# uSlices_v3_1.net
KiCad netlist of a schematic drawn in EAGLE
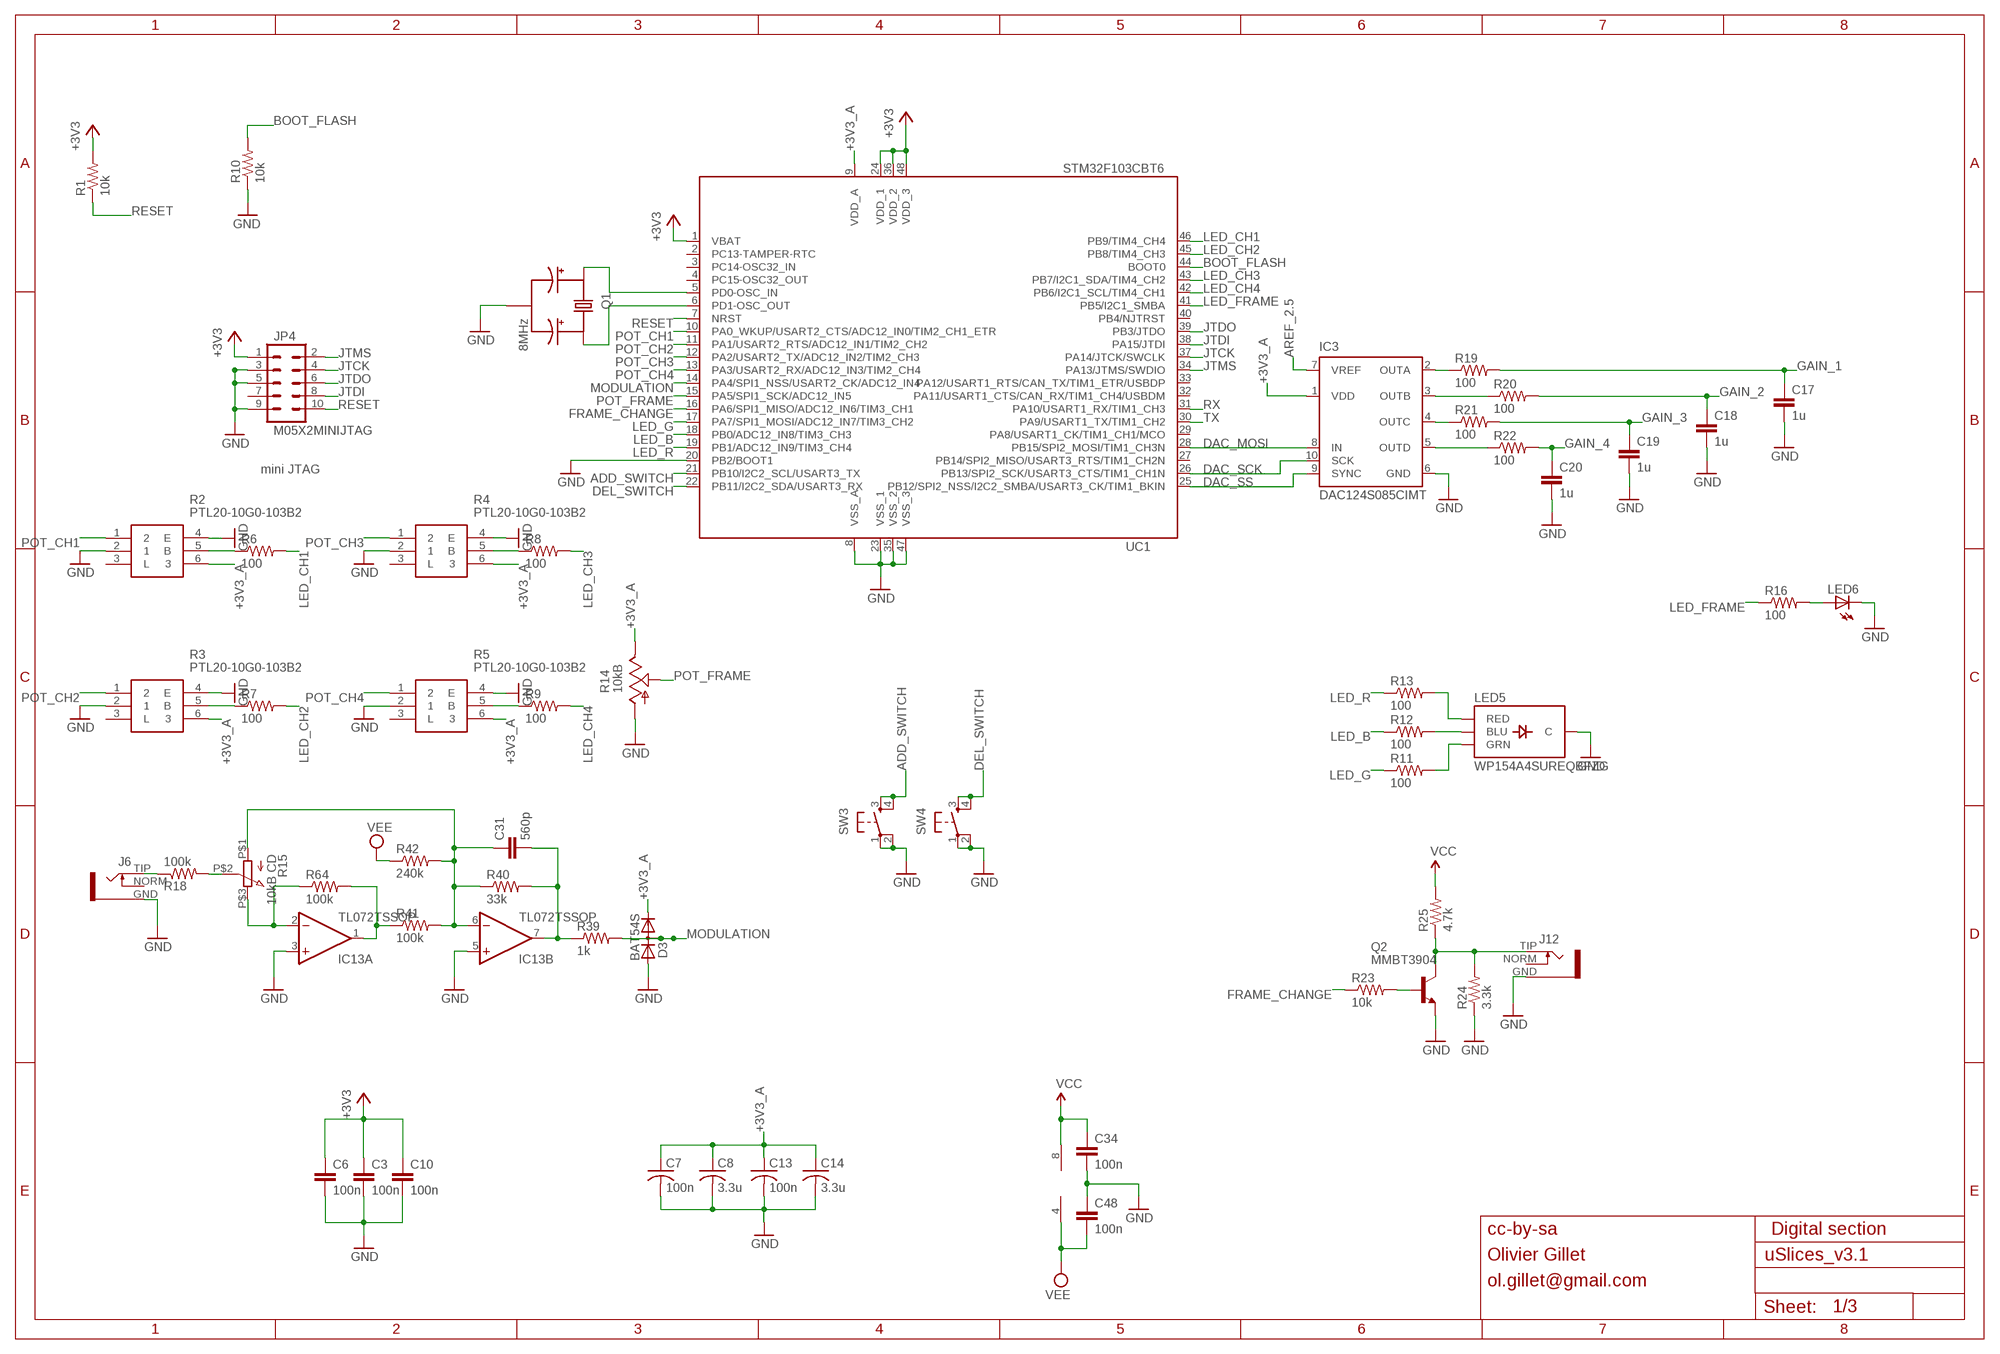
[diagram p0: schematic, sheet 1]
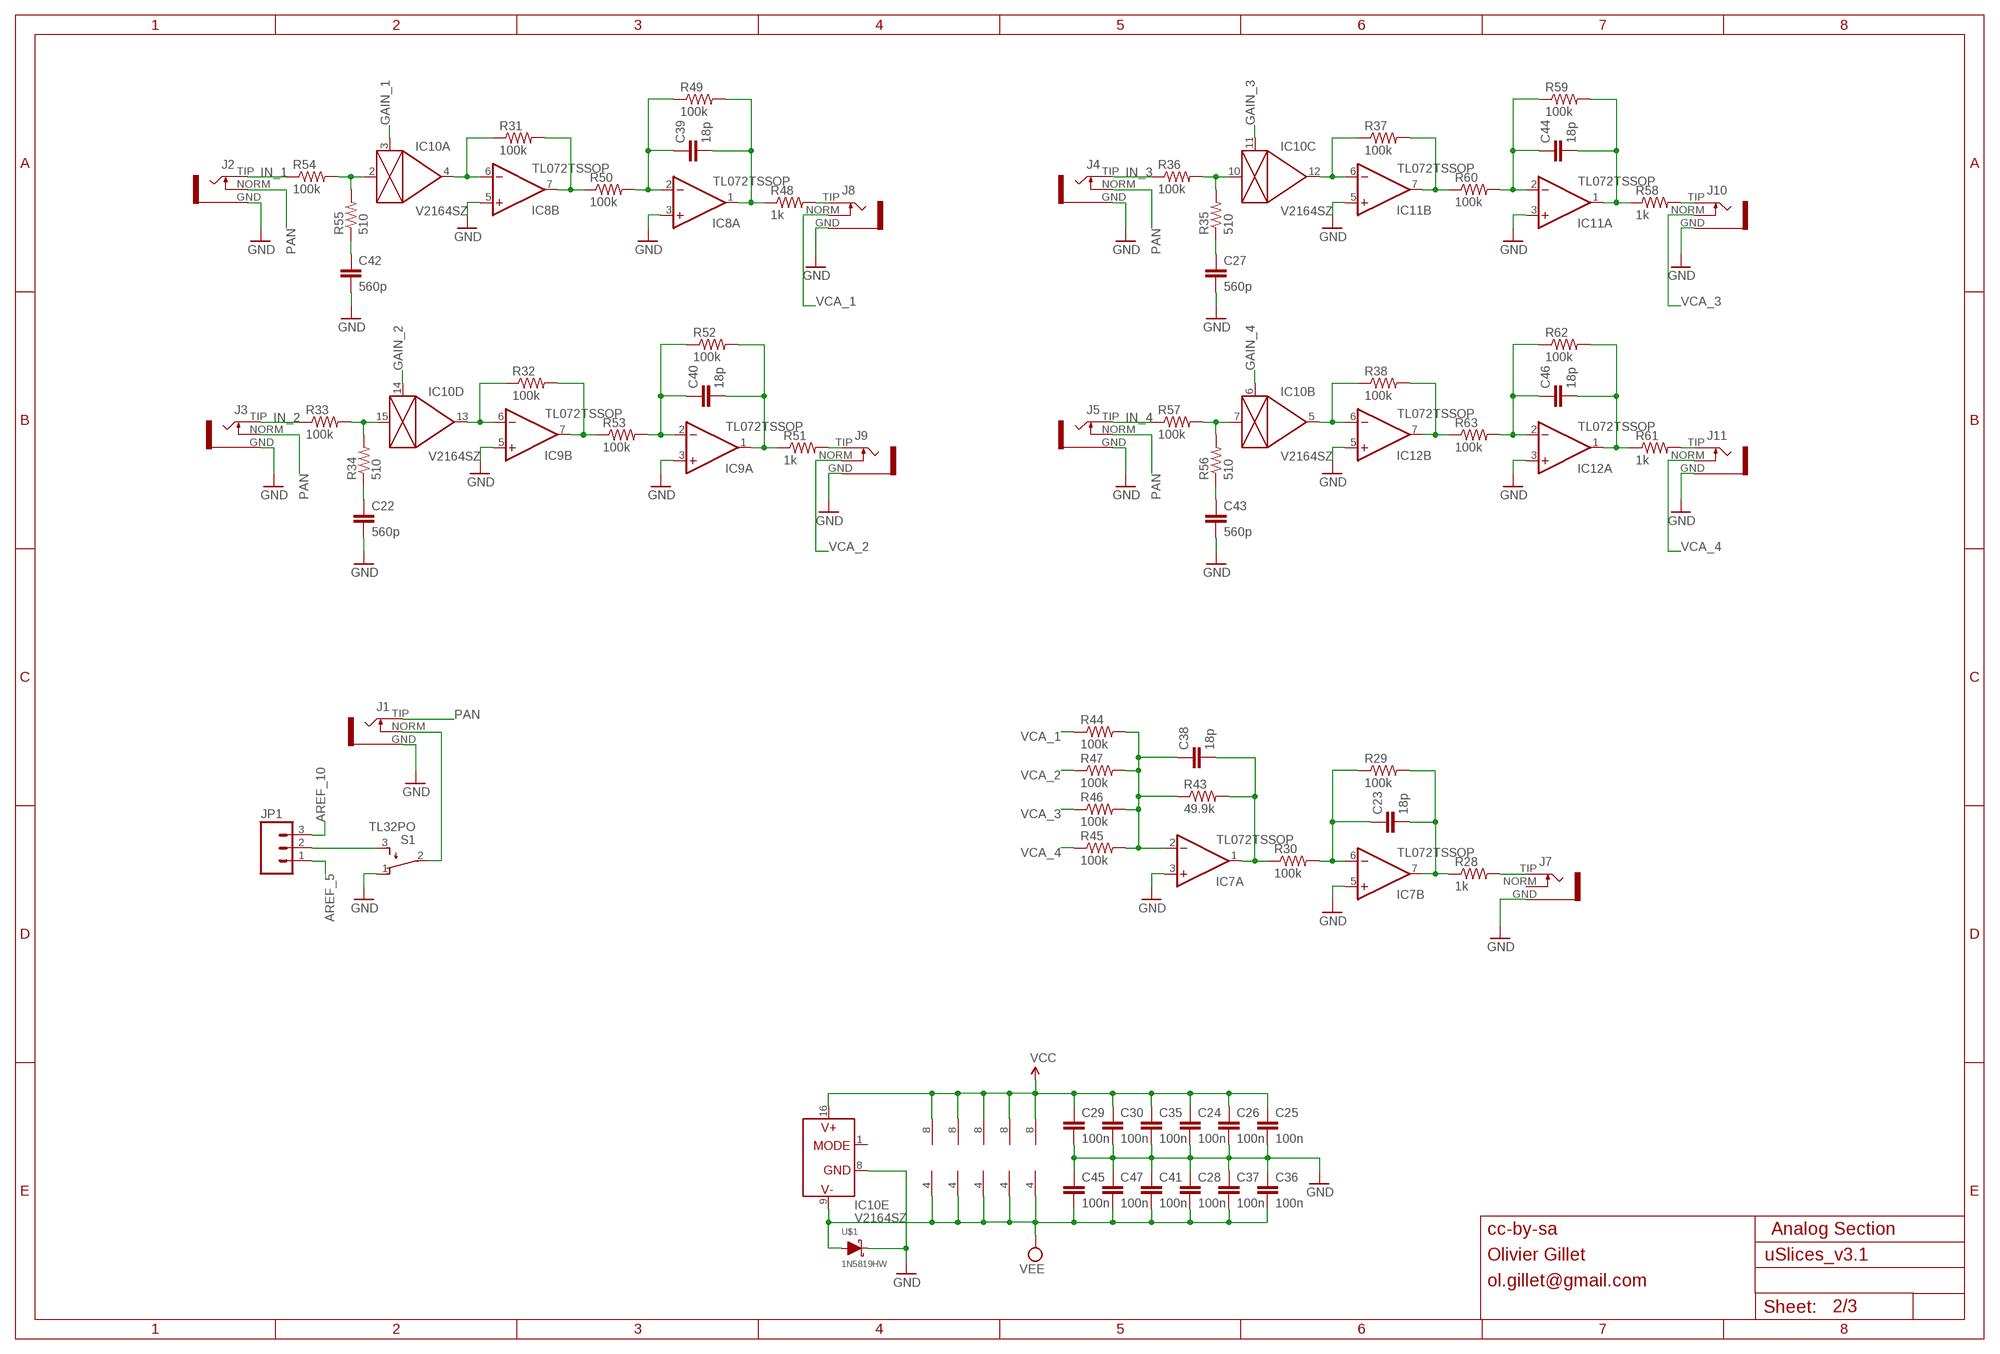
[diagram p1: schematic, sheet 2]
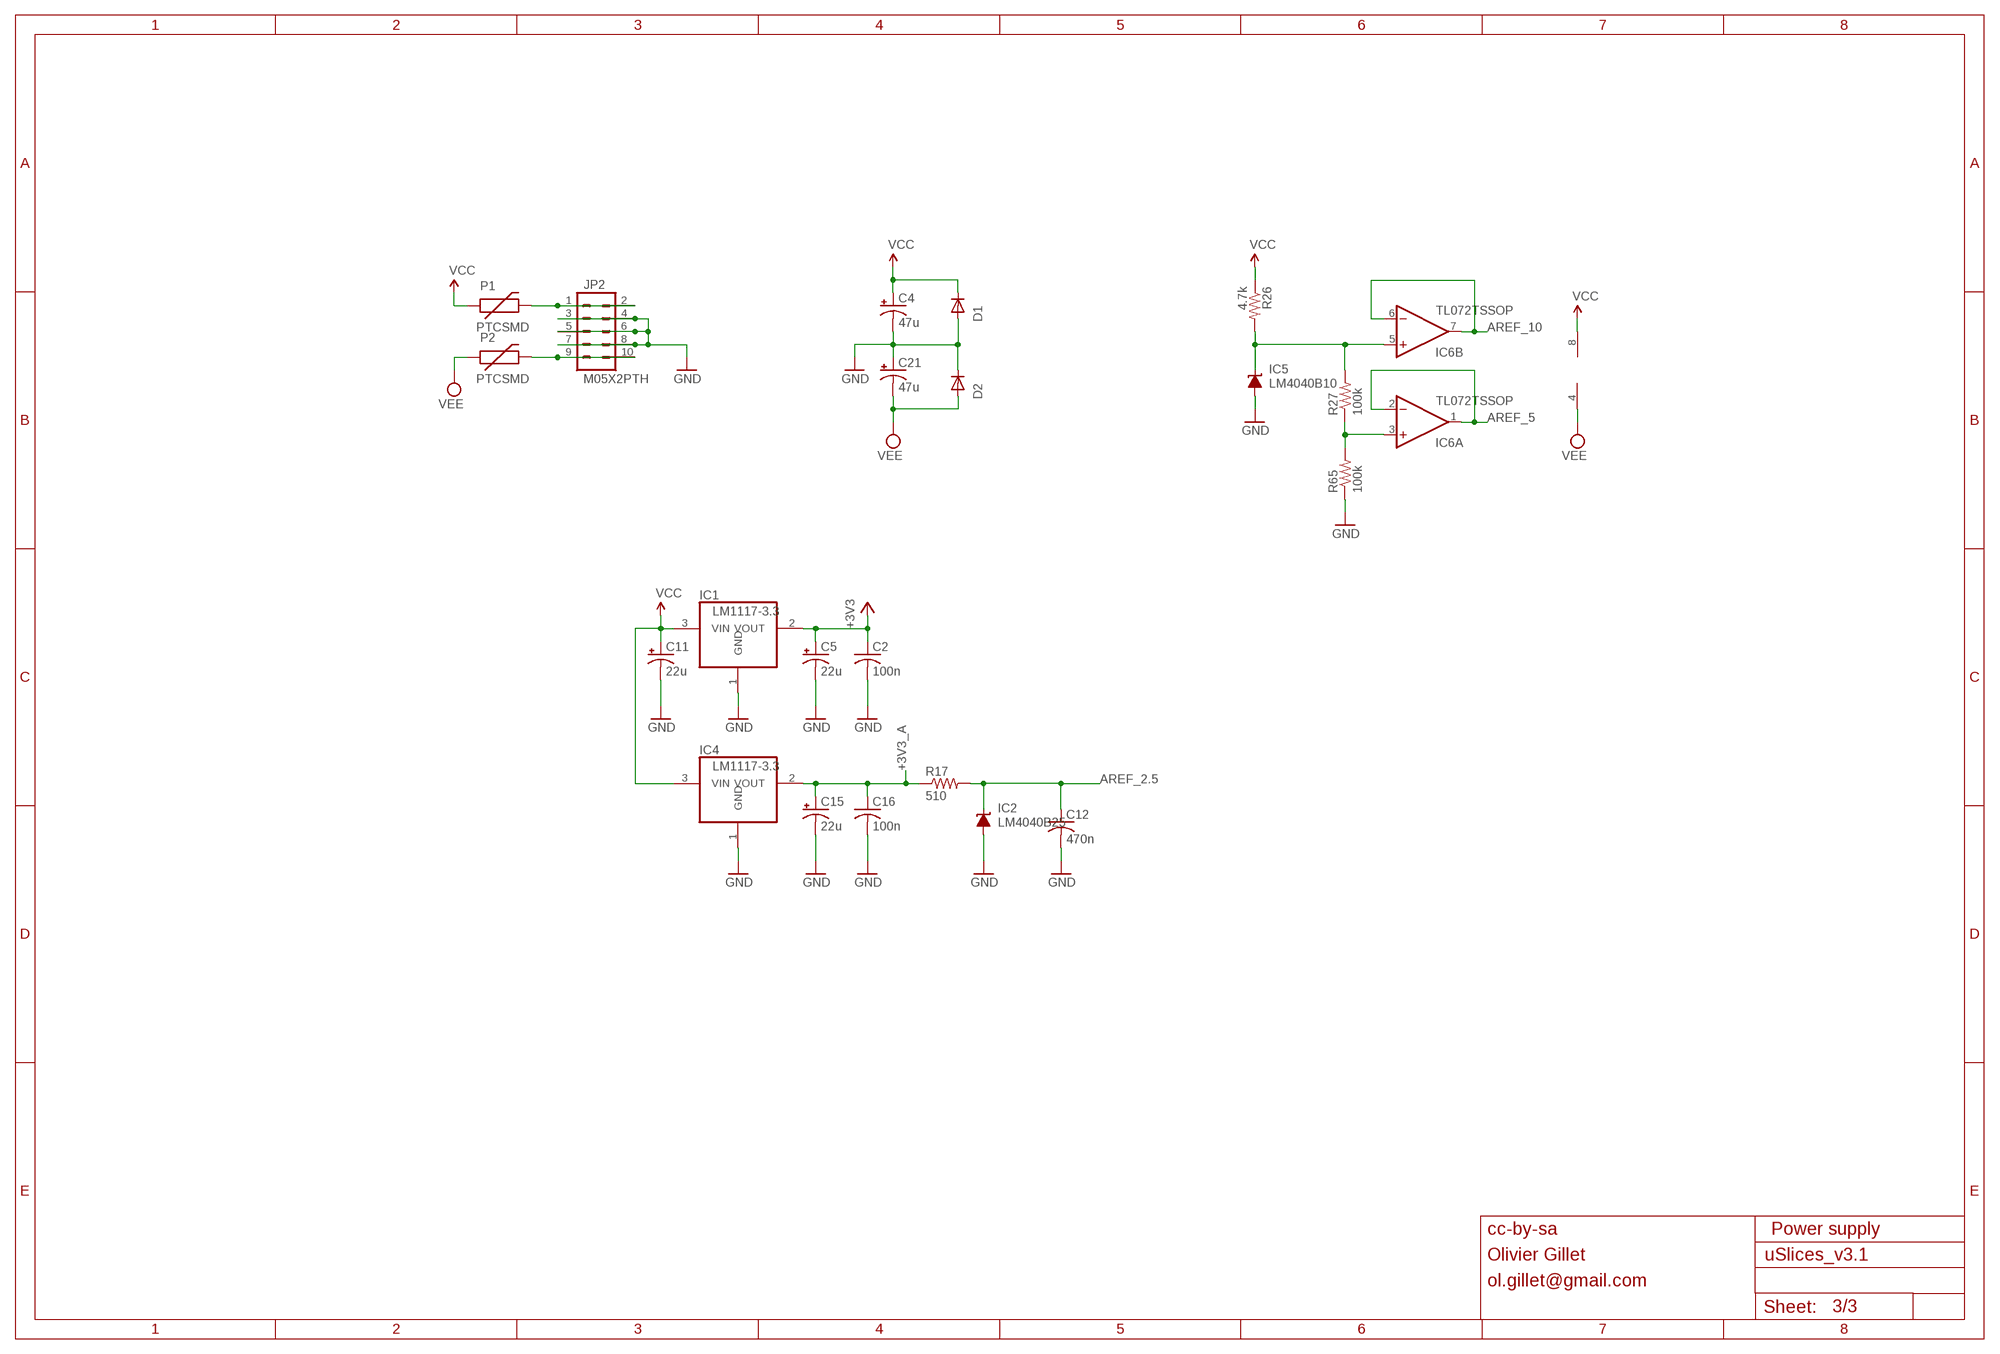
[diagram p2: schematic, sheet 3]

(export (version "E")
  (design (tool "Eeschema 10.0.6"))
  (components
    (comp (ref "C2")
      (value "100n")
      (footprint "eagle-import:C0603")
      (libsource (lib "eagle-import") (part "C-USC0603"))
    )
    (comp (ref "C4")
      (value "47u")
      (footprint "eagle-import:PANASONIC_D")
      (libsource (lib "eagle-import") (part "CPOL-USD"))
    )
    (comp (ref "C5")
      (value "22u")
      (footprint "eagle-import:PANASONIC_C")
      (libsource (lib "eagle-import") (part "CPOL-USC"))
    )
    (comp (ref "C11")
      (value "22u")
      (footprint "eagle-import:PANASONIC_C")
      (libsource (lib "eagle-import") (part "CPOL-USC"))
    )
    (comp (ref "C12")
      (value "470n")
      (footprint "eagle-import:C0603")
      (libsource (lib "eagle-import") (part "C-USC0603"))
    )
    (comp (ref "C15")
      (value "22u")
      (footprint "eagle-import:PANASONIC_C")
      (libsource (lib "eagle-import") (part "CPOL-USC"))
    )
    (comp (ref "C16")
      (value "100n")
      (footprint "eagle-import:C0603")
      (libsource (lib "eagle-import") (part "C-USC0603"))
    )
    (comp (ref "C21")
      (value "47u")
      (footprint "eagle-import:PANASONIC_D")
      (libsource (lib "eagle-import") (part "CPOL-USD"))
    )
    (comp (ref "D1")
      (value "1N5819HW")
      (footprint "eagle-import:SOD123")
      (libsource (lib "eagle-import") (part "DIODE-SOD123"))
    )
    (comp (ref "D2")
      (value "1N5819HW")
      (footprint "eagle-import:SOD123")
      (libsource (lib "eagle-import") (part "DIODE-SOD123"))
    )
    (comp (ref "IC1")
      (value "LM1117-3.3")
      (footprint "eagle-import:SOT223")
      (libsource (lib "eagle-import") (part "REG1117"))
    )
    (comp (ref "IC2")
      (value "LM4040B25")
      (footprint "eagle-import:DBZ_R-PDSO-G3")
      (libsource (lib "eagle-import") (part "LM4041DBZB12"))
    )
    (comp (ref "IC4")
      (value "LM1117-3.3")
      (footprint "eagle-import:SOT223")
      (libsource (lib "eagle-import") (part "REG1117"))
    )
    (comp (ref "IC5")
      (value "LM4040B10")
      (footprint "eagle-import:DBZ_R-PDSO-G3")
      (libsource (lib "eagle-import") (part "LM4041DBZB12"))
    )
    (comp (ref "IC6")
      (value "TL072TSSOP")
      (footprint "eagle-import:TSSOP-8")
      (libsource (lib "eagle-import") (part "TL072TSSOP"))
    )
    (comp (ref "JP2")
      (value "M05X2PTH")
      (footprint "eagle-import:AVR_ICSP")
      (libsource (lib "eagle-import") (part "M05X2PTH"))
    )
    (comp (ref "P1")
      (value "PTCSMD")
      (footprint "eagle-import:PTC-1206")
      (libsource (lib "eagle-import") (part "PTCSMD"))
    )
    (comp (ref "P2")
      (value "PTCSMD")
      (footprint "eagle-import:PTC-1206")
      (libsource (lib "eagle-import") (part "PTCSMD"))
    )
    (comp (ref "R17")
      (value "510")
      (footprint "eagle-import:R0603")
      (libsource (lib "eagle-import") (part "R-US_R0603"))
    )
    (comp (ref "R26")
      (value "4.7k")
      (footprint "eagle-import:R0603")
      (libsource (lib "eagle-import") (part "R-US_R0603"))
    )
    (comp (ref "R27")
      (value "100k")
      (footprint "eagle-import:R0603")
      (libsource (lib "eagle-import") (part "R-US_R0603"))
    )
    (comp (ref "R65")
      (value "100k")
      (footprint "eagle-import:R0603")
      (libsource (lib "eagle-import") (part "R-US_R0603"))
    )
    (comp (ref "C22")
      (value "560p")
      (footprint "eagle-import:PARTS_AMAN_RESISTOR_0603")
      (libsource (lib "eagle-import") (part "PARTS_AMAN_CAPACITOR"))
    )
    (comp (ref "C23")
      (value "18p")
      (footprint "eagle-import:PARTS_AMAN_RESISTOR_0603")
      (libsource (lib "eagle-import") (part "PARTS_AMAN_CAPACITOR"))
    )
    (comp (ref "C24")
      (value "100n")
      (footprint "eagle-import:PARTS_AMAN_RESISTOR_0603")
      (libsource (lib "eagle-import") (part "PARTS_AMAN_CAPACITOR"))
    )
    (comp (ref "C25")
      (value "100n")
      (footprint "eagle-import:PARTS_AMAN_RESISTOR_0603")
      (libsource (lib "eagle-import") (part "PARTS_AMAN_CAPACITOR"))
    )
    (comp (ref "C26")
      (value "100n")
      (footprint "eagle-import:PARTS_AMAN_RESISTOR_0603")
      (libsource (lib "eagle-import") (part "PARTS_AMAN_CAPACITOR"))
    )
    (comp (ref "C27")
      (value "560p")
      (footprint "eagle-import:PARTS_AMAN_RESISTOR_0603")
      (libsource (lib "eagle-import") (part "PARTS_AMAN_CAPACITOR"))
    )
    (comp (ref "C28")
      (value "100n")
      (footprint "eagle-import:PARTS_AMAN_RESISTOR_0603")
      (libsource (lib "eagle-import") (part "PARTS_AMAN_CAPACITOR"))
    )
    (comp (ref "C29")
      (value "100n")
      (footprint "eagle-import:PARTS_AMAN_RESISTOR_0603")
      (libsource (lib "eagle-import") (part "PARTS_AMAN_CAPACITOR"))
    )
    (comp (ref "C30")
      (value "100n")
      (footprint "eagle-import:PARTS_AMAN_RESISTOR_0603")
      (libsource (lib "eagle-import") (part "PARTS_AMAN_CAPACITOR"))
    )
    (comp (ref "C35")
      (value "100n")
      (footprint "eagle-import:PARTS_AMAN_RESISTOR_0603")
      (libsource (lib "eagle-import") (part "PARTS_AMAN_CAPACITOR"))
    )
    (comp (ref "C36")
      (value "100n")
      (footprint "eagle-import:PARTS_AMAN_RESISTOR_0603")
      (libsource (lib "eagle-import") (part "PARTS_AMAN_CAPACITOR"))
    )
    (comp (ref "C37")
      (value "100n")
      (footprint "eagle-import:PARTS_AMAN_RESISTOR_0603")
      (libsource (lib "eagle-import") (part "PARTS_AMAN_CAPACITOR"))
    )
    (comp (ref "C38")
      (value "18p")
      (footprint "eagle-import:PARTS_AMAN_RESISTOR_0603")
      (libsource (lib "eagle-import") (part "PARTS_AMAN_CAPACITOR"))
    )
    (comp (ref "C39")
      (value "18p")
      (footprint "eagle-import:PARTS_AMAN_RESISTOR_0603")
      (libsource (lib "eagle-import") (part "PARTS_AMAN_CAPACITOR"))
    )
    (comp (ref "C40")
      (value "18p")
      (footprint "eagle-import:PARTS_AMAN_RESISTOR_0603")
      (libsource (lib "eagle-import") (part "PARTS_AMAN_CAPACITOR"))
    )
    (comp (ref "C41")
      (value "100n")
      (footprint "eagle-import:PARTS_AMAN_RESISTOR_0603")
      (libsource (lib "eagle-import") (part "PARTS_AMAN_CAPACITOR"))
    )
    (comp (ref "C42")
      (value "560p")
      (footprint "eagle-import:PARTS_AMAN_RESISTOR_0603")
      (libsource (lib "eagle-import") (part "PARTS_AMAN_CAPACITOR"))
    )
    (comp (ref "C43")
      (value "560p")
      (footprint "eagle-import:PARTS_AMAN_RESISTOR_0603")
      (libsource (lib "eagle-import") (part "PARTS_AMAN_CAPACITOR"))
    )
    (comp (ref "C44")
      (value "18p")
      (footprint "eagle-import:PARTS_AMAN_RESISTOR_0603")
      (libsource (lib "eagle-import") (part "PARTS_AMAN_CAPACITOR"))
    )
    (comp (ref "C45")
      (value "100n")
      (footprint "eagle-import:PARTS_AMAN_RESISTOR_0603")
      (libsource (lib "eagle-import") (part "PARTS_AMAN_CAPACITOR"))
    )
    (comp (ref "C46")
      (value "18p")
      (footprint "eagle-import:PARTS_AMAN_RESISTOR_0603")
      (libsource (lib "eagle-import") (part "PARTS_AMAN_CAPACITOR"))
    )
    (comp (ref "C47")
      (value "100n")
      (footprint "eagle-import:PARTS_AMAN_RESISTOR_0603")
      (libsource (lib "eagle-import") (part "PARTS_AMAN_CAPACITOR"))
    )
    (comp (ref "IC7")
      (value "TL072TSSOP")
      (footprint "eagle-import:TSSOP-8")
      (libsource (lib "eagle-import") (part "TL072TSSOP"))
    )
    (comp (ref "IC8")
      (value "TL072TSSOP")
      (footprint "eagle-import:TSSOP-8")
      (libsource (lib "eagle-import") (part "TL072TSSOP"))
    )
    (comp (ref "IC9")
      (value "TL072TSSOP")
      (footprint "eagle-import:TSSOP-8")
      (libsource (lib "eagle-import") (part "TL072TSSOP"))
    )
    (comp (ref "IC10")
      (value "V2164SZ")
      (footprint "eagle-import:SOIC16N")
      (libsource (lib "eagle-import") (part "SSM2164S"))
    )
    (comp (ref "IC11")
      (value "TL072TSSOP")
      (footprint "eagle-import:TSSOP-8")
      (libsource (lib "eagle-import") (part "TL072TSSOP"))
    )
    (comp (ref "IC12")
      (value "TL072TSSOP")
      (footprint "eagle-import:TSSOP-8")
      (libsource (lib "eagle-import") (part "TL072TSSOP"))
    )
    (comp (ref "J1")
      (value "INSTRUO_S_JACK_S2_INV")
      (footprint "eagle-import:INSTRUO_S_JACK_S2_INV")
      (libsource (lib "eagle-import") (part "INSTRUO_S_JACK_S2_INV"))
    )
    (comp (ref "J2")
      (value "INSTRUO_S_JACK_S2_INV")
      (footprint "eagle-import:INSTRUO_S_JACK_S2_INV")
      (libsource (lib "eagle-import") (part "INSTRUO_S_JACK_S2_INV"))
    )
    (comp (ref "J3")
      (value "INSTRUO_S_JACK_S2_INV")
      (footprint "eagle-import:INSTRUO_S_JACK_S2_INV")
      (libsource (lib "eagle-import") (part "INSTRUO_S_JACK_S2_INV"))
    )
    (comp (ref "J4")
      (value "INSTRUO_S_JACK_S2_INV")
      (footprint "eagle-import:INSTRUO_S_JACK_S2_INV")
      (libsource (lib "eagle-import") (part "INSTRUO_S_JACK_S2_INV"))
    )
    (comp (ref "J5")
      (value "INSTRUO_S_JACK_S2_INV")
      (footprint "eagle-import:INSTRUO_S_JACK_S2_INV")
      (libsource (lib "eagle-import") (part "INSTRUO_S_JACK_S2_INV"))
    )
    (comp (ref "J7")
      (value "INSTRUO_S_JACK_S2_INV")
      (footprint "eagle-import:INSTRUO_S_JACK_S2_INV")
      (libsource (lib "eagle-import") (part "INSTRUO_S_JACK_S2_INV"))
    )
    (comp (ref "J8")
      (value "INSTRUO_S_JACK_S2_INV")
      (footprint "eagle-import:INSTRUO_S_JACK_S2_INV")
      (libsource (lib "eagle-import") (part "INSTRUO_S_JACK_S2_INV"))
    )
    (comp (ref "J9")
      (value "INSTRUO_S_JACK_S2_INV")
      (footprint "eagle-import:INSTRUO_S_JACK_S2_INV")
      (libsource (lib "eagle-import") (part "INSTRUO_S_JACK_S2_INV"))
    )
    (comp (ref "J10")
      (value "INSTRUO_S_JACK_S2_INV")
      (footprint "eagle-import:INSTRUO_S_JACK_S2_INV")
      (libsource (lib "eagle-import") (part "INSTRUO_S_JACK_S2_INV"))
    )
    (comp (ref "J11")
      (value "INSTRUO_S_JACK_S2_INV")
      (footprint "eagle-import:INSTRUO_S_JACK_S2_INV")
      (libsource (lib "eagle-import") (part "INSTRUO_S_JACK_S2_INV"))
    )
    (comp (ref "JP1")
      (value "M03PTH")
      (footprint "eagle-import:1X03")
      (libsource (lib "eagle-import") (part "M03PTH"))
    )
    (comp (ref "R28")
      (value "1k")
      (footprint "eagle-import:PARTS_AMAN_RESISTOR_0603")
      (libsource (lib "eagle-import") (part "PARTS_AMAN_RESISTOR"))
    )
    (comp (ref "R29")
      (value "100k")
      (footprint "eagle-import:PARTS_AMAN_RESISTOR_0603")
      (libsource (lib "eagle-import") (part "PARTS_AMAN_RESISTOR"))
    )
    (comp (ref "R30")
      (value "100k")
      (footprint "eagle-import:PARTS_AMAN_RESISTOR_0603")
      (libsource (lib "eagle-import") (part "PARTS_AMAN_RESISTOR"))
    )
    (comp (ref "R31")
      (value "100k")
      (footprint "eagle-import:PARTS_AMAN_RESISTOR_0603")
      (libsource (lib "eagle-import") (part "PARTS_AMAN_RESISTOR"))
    )
    (comp (ref "R32")
      (value "100k")
      (footprint "eagle-import:PARTS_AMAN_RESISTOR_0603")
      (libsource (lib "eagle-import") (part "PARTS_AMAN_RESISTOR"))
    )
    (comp (ref "R33")
      (value "100k")
      (footprint "eagle-import:PARTS_AMAN_RESISTOR_0603")
      (libsource (lib "eagle-import") (part "PARTS_AMAN_RESISTOR"))
    )
    (comp (ref "R34")
      (value "510")
      (footprint "eagle-import:PARTS_AMAN_RESISTOR_0603")
      (libsource (lib "eagle-import") (part "PARTS_AMAN_RESISTOR"))
    )
    (comp (ref "R35")
      (value "510")
      (footprint "eagle-import:PARTS_AMAN_RESISTOR_0603")
      (libsource (lib "eagle-import") (part "PARTS_AMAN_RESISTOR"))
    )
    (comp (ref "R36")
      (value "100k")
      (footprint "eagle-import:PARTS_AMAN_RESISTOR_0603")
      (libsource (lib "eagle-import") (part "PARTS_AMAN_RESISTOR"))
    )
    (comp (ref "R37")
      (value "100k")
      (footprint "eagle-import:PARTS_AMAN_RESISTOR_0603")
      (libsource (lib "eagle-import") (part "PARTS_AMAN_RESISTOR"))
    )
    (comp (ref "R38")
      (value "100k")
      (footprint "eagle-import:PARTS_AMAN_RESISTOR_0603")
      (libsource (lib "eagle-import") (part "PARTS_AMAN_RESISTOR"))
    )
    (comp (ref "R43")
      (value "49.9k")
      (footprint "eagle-import:PARTS_AMAN_RESISTOR_0603")
      (libsource (lib "eagle-import") (part "PARTS_AMAN_RESISTOR"))
    )
    (comp (ref "R44")
      (value "100k")
      (footprint "eagle-import:PARTS_AMAN_RESISTOR_0603")
      (libsource (lib "eagle-import") (part "PARTS_AMAN_RESISTOR"))
    )
    (comp (ref "R45")
      (value "100k")
      (footprint "eagle-import:PARTS_AMAN_RESISTOR_0603")
      (libsource (lib "eagle-import") (part "PARTS_AMAN_RESISTOR"))
    )
    (comp (ref "R46")
      (value "100k")
      (footprint "eagle-import:PARTS_AMAN_RESISTOR_0603")
      (libsource (lib "eagle-import") (part "PARTS_AMAN_RESISTOR"))
    )
    (comp (ref "R47")
      (value "100k")
      (footprint "eagle-import:PARTS_AMAN_RESISTOR_0603")
      (libsource (lib "eagle-import") (part "PARTS_AMAN_RESISTOR"))
    )
    (comp (ref "R48")
      (value "1k")
      (footprint "eagle-import:PARTS_AMAN_RESISTOR_0603")
      (libsource (lib "eagle-import") (part "PARTS_AMAN_RESISTOR"))
    )
    (comp (ref "R49")
      (value "100k")
      (footprint "eagle-import:PARTS_AMAN_RESISTOR_0603")
      (libsource (lib "eagle-import") (part "PARTS_AMAN_RESISTOR"))
    )
    (comp (ref "R50")
      (value "100k")
      (footprint "eagle-import:PARTS_AMAN_RESISTOR_0603")
      (libsource (lib "eagle-import") (part "PARTS_AMAN_RESISTOR"))
    )
    (comp (ref "R51")
      (value "1k")
      (footprint "eagle-import:PARTS_AMAN_RESISTOR_0603")
      (libsource (lib "eagle-import") (part "PARTS_AMAN_RESISTOR"))
    )
    (comp (ref "R52")
      (value "100k")
      (footprint "eagle-import:PARTS_AMAN_RESISTOR_0603")
      (libsource (lib "eagle-import") (part "PARTS_AMAN_RESISTOR"))
    )
    (comp (ref "R53")
      (value "100k")
      (footprint "eagle-import:PARTS_AMAN_RESISTOR_0603")
      (libsource (lib "eagle-import") (part "PARTS_AMAN_RESISTOR"))
    )
    (comp (ref "R54")
      (value "100k")
      (footprint "eagle-import:PARTS_AMAN_RESISTOR_0603")
      (libsource (lib "eagle-import") (part "PARTS_AMAN_RESISTOR"))
    )
    (comp (ref "R55")
      (value "510")
      (footprint "eagle-import:PARTS_AMAN_RESISTOR_0603")
      (libsource (lib "eagle-import") (part "PARTS_AMAN_RESISTOR"))
    )
    (comp (ref "R56")
      (value "510")
      (footprint "eagle-import:PARTS_AMAN_RESISTOR_0603")
      (libsource (lib "eagle-import") (part "PARTS_AMAN_RESISTOR"))
    )
    (comp (ref "R57")
      (value "100k")
      (footprint "eagle-import:PARTS_AMAN_RESISTOR_0603")
      (libsource (lib "eagle-import") (part "PARTS_AMAN_RESISTOR"))
    )
    (comp (ref "R58")
      (value "1k")
      (footprint "eagle-import:PARTS_AMAN_RESISTOR_0603")
      (libsource (lib "eagle-import") (part "PARTS_AMAN_RESISTOR"))
    )
    (comp (ref "R59")
      (value "100k")
      (footprint "eagle-import:PARTS_AMAN_RESISTOR_0603")
      (libsource (lib "eagle-import") (part "PARTS_AMAN_RESISTOR"))
    )
    (comp (ref "R60")
      (value "100k")
      (footprint "eagle-import:PARTS_AMAN_RESISTOR_0603")
      (libsource (lib "eagle-import") (part "PARTS_AMAN_RESISTOR"))
    )
    (comp (ref "R61")
      (value "1k")
      (footprint "eagle-import:PARTS_AMAN_RESISTOR_0603")
      (libsource (lib "eagle-import") (part "PARTS_AMAN_RESISTOR"))
    )
    (comp (ref "R62")
      (value "100k")
      (footprint "eagle-import:PARTS_AMAN_RESISTOR_0603")
      (libsource (lib "eagle-import") (part "PARTS_AMAN_RESISTOR"))
    )
    (comp (ref "R63")
      (value "100k")
      (footprint "eagle-import:PARTS_AMAN_RESISTOR_0603")
      (libsource (lib "eagle-import") (part "PARTS_AMAN_RESISTOR"))
    )
    (comp (ref "S1")
      (value "TL32PO")
      (footprint "eagle-import:TL3XPO")
      (libsource (lib "eagle-import") (part "TL32PO"))
    )
    (comp (ref "U$1")
      (value "1N5819HW")
      (footprint "eagle-import:SOD123")
      (fields (field (name "MPN") "1N5819HW-7-F"))
      (libsource (lib "eagle-import") (part "1N5819HW"))
    )
    (comp (ref "C3")
      (value "100n")
      (footprint "eagle-import:PARTS_AMAN_RESISTOR_0603")
      (libsource (lib "eagle-import") (part "PARTS_AMAN_CAPACITOR"))
    )
    (comp (ref "C6")
      (value "100n")
      (footprint "eagle-import:PARTS_AMAN_RESISTOR_0603")
      (libsource (lib "eagle-import") (part "PARTS_AMAN_CAPACITOR"))
    )
    (comp (ref "C7")
      (value "100n")
      (footprint "eagle-import:C0603")
      (libsource (lib "eagle-import") (part "C-USC0603"))
    )
    (comp (ref "C8")
      (value "3.3u")
      (footprint "eagle-import:C0603")
      (libsource (lib "eagle-import") (part "C-USC0603"))
    )
    (comp (ref "C10")
      (value "100n")
      (footprint "eagle-import:PARTS_AMAN_RESISTOR_0603")
      (libsource (lib "eagle-import") (part "PARTS_AMAN_CAPACITOR"))
    )
    (comp (ref "C13")
      (value "100n")
      (footprint "eagle-import:C0603")
      (libsource (lib "eagle-import") (part "C-USC0603"))
    )
    (comp (ref "C14")
      (value "3.3u")
      (footprint "eagle-import:C0603")
      (libsource (lib "eagle-import") (part "C-USC0603"))
    )
    (comp (ref "C17")
      (value "1u")
      (footprint "eagle-import:PARTS_AMAN_RESISTOR_0603")
      (libsource (lib "eagle-import") (part "PARTS_AMAN_CAPACITOR"))
    )
    (comp (ref "C18")
      (value "1u")
      (footprint "eagle-import:PARTS_AMAN_RESISTOR_0603")
      (libsource (lib "eagle-import") (part "PARTS_AMAN_CAPACITOR"))
    )
    (comp (ref "C19")
      (value "1u")
      (footprint "eagle-import:PARTS_AMAN_RESISTOR_0603")
      (libsource (lib "eagle-import") (part "PARTS_AMAN_CAPACITOR"))
    )
    (comp (ref "C20")
      (value "1u")
      (footprint "eagle-import:PARTS_AMAN_RESISTOR_0603")
      (libsource (lib "eagle-import") (part "PARTS_AMAN_CAPACITOR"))
    )
    (comp (ref "C31")
      (value "560p")
      (footprint "eagle-import:PARTS_AMAN_RESISTOR_0603")
      (libsource (lib "eagle-import") (part "PARTS_AMAN_CAPACITOR"))
    )
    (comp (ref "C34")
      (value "100n")
      (footprint "eagle-import:PARTS_AMAN_RESISTOR_0603")
      (libsource (lib "eagle-import") (part "PARTS_AMAN_CAPACITOR"))
    )
    (comp (ref "C48")
      (value "100n")
      (footprint "eagle-import:PARTS_AMAN_RESISTOR_0603")
      (libsource (lib "eagle-import") (part "PARTS_AMAN_CAPACITOR"))
    )
    (comp (ref "D3")
      (value "BAT54S")
      (footprint "eagle-import:SOT23")
      (libsource (lib "eagle-import") (part "DIODE_2CACA-SOT23"))
    )
    (comp (ref "IC3")
      (value "DAC124S085CIMT")
      (footprint "eagle-import:MSOP10")
      (libsource (lib "eagle-import") (part "DAC124S085CIMT"))
    )
    (comp (ref "IC13")
      (value "TL072TSSOP")
      (footprint "eagle-import:TSSOP-8")
      (libsource (lib "eagle-import") (part "TL072TSSOP"))
    )
    (comp (ref "J6")
      (value "INSTRUO_S_JACK_S2_INV")
      (footprint "eagle-import:INSTRUO_S_JACK_S2_INV")
      (libsource (lib "eagle-import") (part "INSTRUO_S_JACK_S2_INV"))
    )
    (comp (ref "J12")
      (value "INSTRUO_S_JACK_S2_INV")
      (footprint "eagle-import:INSTRUO_S_JACK_S2_INV")
      (libsource (lib "eagle-import") (part "INSTRUO_S_JACK_S2_INV"))
    )
    (comp (ref "JP4")
      (value "M05X2MINIJTAG")
      (footprint "eagle-import:2X5-1.27")
      (libsource (lib "eagle-import") (part "M05X2MINIJTAG"))
    )
    (comp (ref "LED5")
      (value "WP154A4SUREQBFZG")
      (footprint "eagle-import:LED-TRICOLOR-THROUGHHOLE")
      (libsource (lib "eagle-import") (part "LED-TRICOLOR-THROUGHHOLE"))
    )
    (comp (ref "LED6")
      (value "LED3MM")
      (footprint "eagle-import:LED3MM")
      (libsource (lib "eagle-import") (part "LED3MM"))
    )
    (comp (ref "Q1")
      (value "8MHz")
      (footprint "eagle-import:INSTRUO_CRYSTAL_SMALLER")
      (libsource (lib "eagle-import") (part "INSTRUO_CRYSTAL_SMALLER"))
    )
    (comp (ref "Q2")
      (value "MMBT3904")
      (footprint "eagle-import:SOT23-BEC")
      (libsource (lib "eagle-import") (part "-NPN-SOT23-BECMMBT3904LT1"))
    )
    (comp (ref "R1")
      (value "10k")
      (footprint "eagle-import:PARTS_AMAN_RESISTOR_0603")
      (libsource (lib "eagle-import") (part "PARTS_AMAN_RESISTOR"))
    )
    (comp (ref "R2")
      (value "PTL20-10G0-103B2")
      (footprint "eagle-import:PTL2010G0103B2")
      (fields (field (name "ARROW_PART_NUMBER") "PTL30-10O1-103B2"))
      (libsource (lib "eagle-import") (part "PTL20-10G0-103B2"))
    )
    (comp (ref "R3")
      (value "PTL20-10G0-103B2")
      (footprint "eagle-import:PTL2010G0103B2")
      (fields (field (name "ARROW_PART_NUMBER") "PTL30-10O1-103B2"))
      (libsource (lib "eagle-import") (part "PTL20-10G0-103B2"))
    )
    (comp (ref "R4")
      (value "PTL20-10G0-103B2")
      (footprint "eagle-import:PTL2010G0103B2")
      (fields (field (name "ARROW_PART_NUMBER") "PTL30-10O1-103B2"))
      (libsource (lib "eagle-import") (part "PTL20-10G0-103B2"))
    )
    (comp (ref "R5")
      (value "PTL20-10G0-103B2")
      (footprint "eagle-import:PTL2010G0103B2")
      (fields (field (name "ARROW_PART_NUMBER") "PTL30-10O1-103B2"))
      (libsource (lib "eagle-import") (part "PTL20-10G0-103B2"))
    )
    (comp (ref "R6")
      (value "100")
      (footprint "eagle-import:PARTS_AMAN_RESISTOR_0603")
      (libsource (lib "eagle-import") (part "PARTS_AMAN_RESISTOR"))
    )
    (comp (ref "R7")
      (value "100")
      (footprint "eagle-import:PARTS_AMAN_RESISTOR_0603")
      (libsource (lib "eagle-import") (part "PARTS_AMAN_RESISTOR"))
    )
    (comp (ref "R8")
      (value "100")
      (footprint "eagle-import:PARTS_AMAN_RESISTOR_0603")
      (libsource (lib "eagle-import") (part "PARTS_AMAN_RESISTOR"))
    )
    (comp (ref "R9")
      (value "100")
      (footprint "eagle-import:PARTS_AMAN_RESISTOR_0603")
      (libsource (lib "eagle-import") (part "PARTS_AMAN_RESISTOR"))
    )
    (comp (ref "R10")
      (value "10k")
      (footprint "eagle-import:PARTS_AMAN_RESISTOR_0603")
      (libsource (lib "eagle-import") (part "PARTS_AMAN_RESISTOR"))
    )
    (comp (ref "R11")
      (value "100")
      (footprint "eagle-import:PARTS_AMAN_RESISTOR_0603")
      (libsource (lib "eagle-import") (part "PARTS_AMAN_RESISTOR"))
    )
    (comp (ref "R12")
      (value "100")
      (footprint "eagle-import:PARTS_AMAN_RESISTOR_0603")
      (libsource (lib "eagle-import") (part "PARTS_AMAN_RESISTOR"))
    )
    (comp (ref "R13")
      (value "100")
      (footprint "eagle-import:PARTS_AMAN_RESISTOR_0603")
      (libsource (lib "eagle-import") (part "PARTS_AMAN_RESISTOR"))
    )
    (comp (ref "R14")
      (value "10kB")
      (footprint "eagle-import:ALPS_POT_VERTICAL_PS")
      (libsource (lib "eagle-import") (part "POT_USVERTICAL_PS"))
    )
    (comp (ref "R15")
      (value "10kB CD")
      (footprint "eagle-import:INSTRUO_Q-POT2")
      (libsource (lib "eagle-import") (part "INSTRUO_Q-POT2"))
    )
    (comp (ref "R16")
      (value "100")
      (footprint "eagle-import:PARTS_AMAN_RESISTOR_0603")
      (libsource (lib "eagle-import") (part "PARTS_AMAN_RESISTOR"))
    )
    (comp (ref "R18")
      (value "100k")
      (footprint "eagle-import:R0603")
      (libsource (lib "eagle-import") (part "R-US_R0603"))
    )
    (comp (ref "R19")
      (value "100")
      (footprint "eagle-import:PARTS_AMAN_RESISTOR_0603")
      (libsource (lib "eagle-import") (part "PARTS_AMAN_RESISTOR"))
    )
    (comp (ref "R20")
      (value "100")
      (footprint "eagle-import:PARTS_AMAN_RESISTOR_0603")
      (libsource (lib "eagle-import") (part "PARTS_AMAN_RESISTOR"))
    )
    (comp (ref "R21")
      (value "100")
      (footprint "eagle-import:PARTS_AMAN_RESISTOR_0603")
      (libsource (lib "eagle-import") (part "PARTS_AMAN_RESISTOR"))
    )
    (comp (ref "R22")
      (value "100")
      (footprint "eagle-import:PARTS_AMAN_RESISTOR_0603")
      (libsource (lib "eagle-import") (part "PARTS_AMAN_RESISTOR"))
    )
    (comp (ref "R23")
      (value "10k")
      (footprint "eagle-import:PARTS_AMAN_RESISTOR_0603")
      (libsource (lib "eagle-import") (part "PARTS_AMAN_RESISTOR"))
    )
    (comp (ref "R24")
      (value "3.3k")
      (footprint "eagle-import:PARTS_AMAN_RESISTOR_0603")
      (libsource (lib "eagle-import") (part "PARTS_AMAN_RESISTOR"))
    )
    (comp (ref "R25")
      (value "4.7k")
      (footprint "eagle-import:PARTS_AMAN_RESISTOR_0603")
      (libsource (lib "eagle-import") (part "PARTS_AMAN_RESISTOR"))
    )
    (comp (ref "R39")
      (value "1k")
      (footprint "eagle-import:PARTS_AMAN_RESISTOR_0603")
      (libsource (lib "eagle-import") (part "PARTS_AMAN_RESISTOR"))
    )
    (comp (ref "R40")
      (value "33k")
      (footprint "eagle-import:PARTS_AMAN_RESISTOR_0603")
      (libsource (lib "eagle-import") (part "PARTS_AMAN_RESISTOR"))
    )
    (comp (ref "R41")
      (value "100k")
      (footprint "eagle-import:PARTS_AMAN_RESISTOR_0603")
      (libsource (lib "eagle-import") (part "PARTS_AMAN_RESISTOR"))
    )
    (comp (ref "R42")
      (value "240k")
      (footprint "eagle-import:PARTS_AMAN_RESISTOR_0603")
      (libsource (lib "eagle-import") (part "PARTS_AMAN_RESISTOR"))
    )
    (comp (ref "R64")
      (value "100k")
      (footprint "eagle-import:PARTS_AMAN_RESISTOR_0603")
      (libsource (lib "eagle-import") (part "PARTS_AMAN_RESISTOR"))
    )
    (comp (ref "SW3")
      (value "SPARKFUN_TAC_SWITCHPTH")
      (footprint "eagle-import:SPARKFUN_TACTILE-PTH")
      (libsource (lib "eagle-import") (part "SPARKFUN_TAC_SWITCHPTH"))
    )
    (comp (ref "SW4")
      (value "SPARKFUN_TAC_SWITCHPTH")
      (footprint "eagle-import:SPARKFUN_TACTILE-PTH")
      (libsource (lib "eagle-import") (part "SPARKFUN_TAC_SWITCHPTH"))
    )
    (comp (ref "UC1")
      (value "STM32F103CBT6")
      (footprint "eagle-import:LQFP48")
      (libsource (lib "eagle-import") (part "STM32F103CB"))
    )
  )
  (nets
    (net (code "1") (name "+3V3") (class "Default")
      (node (ref "C10") (pin "1") (pinfunction "1_1") (pintype "passive"))
      (node (ref "C2") (pin "1") (pinfunction "1_1") (pintype "passive"))
      (node (ref "C3") (pin "1") (pinfunction "1_1") (pintype "passive"))
      (node (ref "C5") (pin "+") (pinfunction "+_+") (pintype "passive"))
      (node (ref "C6") (pin "1") (pinfunction "1_1") (pintype "passive"))
      (node (ref "IC1") (pin "2") (pinfunction "VOUT_2") (pintype "output"))
      (node (ref "JP4") (pin "1") (pinfunction "1_1") (pintype "passive"))
      (node (ref "R1") (pin "2") (pinfunction "2_2") (pintype "passive"))
      (node (ref "UC1") (pin "1") (pinfunction "VBAT_1") (pintype "power_in"))
      (node (ref "UC1") (pin "24") (pinfunction "VDD_1_24") (pintype "power_in"))
      (node (ref "UC1") (pin "36") (pinfunction "VDD_2_36") (pintype "power_in"))
      (node (ref "UC1") (pin "48") (pinfunction "VDD_3_48") (pintype "power_in"))
    )
    (net (code "2") (name "+3V3_A") (class "Default")
      (node (ref "C13") (pin "1") (pinfunction "1_1") (pintype "passive"))
      (node (ref "C14") (pin "1") (pinfunction "1_1") (pintype "passive"))
      (node (ref "C15") (pin "+") (pinfunction "+_+") (pintype "passive"))
      (node (ref "C16") (pin "1") (pinfunction "1_1") (pintype "passive"))
      (node (ref "C7") (pin "1") (pinfunction "1_1") (pintype "passive"))
      (node (ref "C8") (pin "1") (pinfunction "1_1") (pintype "passive"))
      (node (ref "D3") (pin "2") (pinfunction "C_2") (pintype "passive"))
      (node (ref "IC3") (pin "1") (pinfunction "VDD_1") (pintype "power_in"))
      (node (ref "IC4") (pin "2") (pinfunction "VOUT_2") (pintype "output"))
      (node (ref "R14") (pin "P$1") (pinfunction "E_P$1") (pintype "passive"))
      (node (ref "R17") (pin "1") (pinfunction "1_1") (pintype "passive"))
      (node (ref "R2") (pin "6") (pinfunction "3_6") (pintype "bidirectional"))
      (node (ref "R3") (pin "6") (pinfunction "3_6") (pintype "bidirectional"))
      (node (ref "R4") (pin "6") (pinfunction "3_6") (pintype "bidirectional"))
      (node (ref "R5") (pin "6") (pinfunction "3_6") (pintype "bidirectional"))
      (node (ref "UC1") (pin "9") (pinfunction "VDD_A_9") (pintype "power_in"))
    )
    (net (code "3") (name "ADD_SWITCH") (class "Default")
      (node (ref "SW3") (pin "3") (pinfunction "3_3") (pintype "passive"))
      (node (ref "SW3") (pin "4") (pinfunction "4_4") (pintype "passive"))
      (node (ref "UC1") (pin "21") (pinfunction "PB10/I2C2_SCL/USART3_TX_21") (pintype "input"))
    )
    (net (code "4") (name "AREF_2.5") (class "Default")
      (node (ref "C12") (pin "1") (pinfunction "1_1") (pintype "passive"))
      (node (ref "IC2") (pin "1") (pinfunction "C_1") (pintype "passive"))
      (node (ref "IC3") (pin "7") (pinfunction "VREF_7") (pintype "bidirectional"))
      (node (ref "R17") (pin "2") (pinfunction "2_2") (pintype "passive"))
    )
    (net (code "5") (name "AREF_5") (class "Default")
      (node (ref "IC6") (pin "1") (pinfunction "OUT_1") (pintype "output"))
      (node (ref "IC6") (pin "2") (pinfunction "-IN_2") (pintype "input"))
      (node (ref "JP1") (pin "1") (pinfunction "1_1") (pintype "passive"))
    )
    (net (code "6") (name "AREF_10") (class "Default")
      (node (ref "IC6") (pin "6") (pinfunction "-IN_6") (pintype "input"))
      (node (ref "IC6") (pin "7") (pinfunction "OUT_7") (pintype "output"))
      (node (ref "JP1") (pin "3") (pinfunction "3_3") (pintype "passive"))
    )
    (net (code "7") (name "BOOT_FLASH") (class "Default")
      (node (ref "R10") (pin "2") (pinfunction "2_2") (pintype "passive"))
      (node (ref "UC1") (pin "44") (pinfunction "BOOT0_44") (pintype "input"))
    )
    (net (code "8") (name "DAC_MOSI") (class "Default")
      (node (ref "IC3") (pin "8") (pinfunction "IN_8") (pintype "input"))
      (node (ref "UC1") (pin "28") (pinfunction "PB15/SPI2_MOSI/TIM1_CH3N_28") (pintype "input"))
    )
    (net (code "9") (name "DAC_SCK") (class "Default")
      (node (ref "IC3") (pin "10") (pinfunction "SCK_10") (pintype "input"))
      (node (ref "UC1") (pin "26") (pinfunction "PB13/SPI2_SCK/USART3_CTS/TIM1_CH1N_26") (pintype "input"))
    )
    (net (code "10") (name "DAC_SS") (class "Default")
      (node (ref "IC3") (pin "9") (pinfunction "SYNC_9") (pintype "input"))
      (node (ref "UC1") (pin "25") (pinfunction "PB12/SPI2_NSS/I2C2_SMBA/USART3_CK/TIM1_BKIN_25") (pintype "input"))
    )
    (net (code "11") (name "DEL_SWITCH") (class "Default")
      (node (ref "SW4") (pin "3") (pinfunction "3_3") (pintype "passive"))
      (node (ref "SW4") (pin "4") (pinfunction "4_4") (pintype "passive"))
      (node (ref "UC1") (pin "22") (pinfunction "PB11/I2C2_SDA/USART3_RX_22") (pintype "input"))
    )
    (net (code "12") (name "FRAME_CHANGE") (class "Default")
      (node (ref "R23") (pin "1") (pinfunction "1_1") (pintype "passive"))
      (node (ref "UC1") (pin "16") (pinfunction "PA6/SPI1_MISO/ADC12_IN6/TIM3_CH1_16") (pintype "bidirectional"))
    )
    (net (code "13") (name "GAIN_1") (class "Default")
      (node (ref "C17") (pin "1") (pinfunction "1_1") (pintype "passive"))
      (node (ref "IC10") (pin "3") (pinfunction "CTRL_3") (pintype "input"))
      (node (ref "R19") (pin "2") (pinfunction "2_2") (pintype "passive"))
    )
    (net (code "14") (name "GAIN_2") (class "Default")
      (node (ref "C18") (pin "1") (pinfunction "1_1") (pintype "passive"))
      (node (ref "IC10") (pin "14") (pinfunction "CTRL_14") (pintype "input"))
      (node (ref "R20") (pin "2") (pinfunction "2_2") (pintype "passive"))
    )
    (net (code "15") (name "GAIN_3") (class "Default")
      (node (ref "C19") (pin "1") (pinfunction "1_1") (pintype "passive"))
      (node (ref "IC10") (pin "11") (pinfunction "CTRL_11") (pintype "input"))
      (node (ref "R21") (pin "2") (pinfunction "2_2") (pintype "passive"))
    )
    (net (code "16") (name "GAIN_4") (class "Default")
      (node (ref "C20") (pin "1") (pinfunction "1_1") (pintype "passive"))
      (node (ref "IC10") (pin "6") (pinfunction "CTRL_6") (pintype "input"))
      (node (ref "R22") (pin "2") (pinfunction "2_2") (pintype "passive"))
    )
    (net (code "17") (name "GND") (class "Default")
      (node (ref "C10") (pin "2") (pinfunction "2_2") (pintype "passive"))
      (node (ref "C11") (pin "-") (pinfunction "-_-") (pintype "passive"))
      (node (ref "C12") (pin "2") (pinfunction "2_2") (pintype "passive"))
      (node (ref "C13") (pin "2") (pinfunction "2_2") (pintype "passive"))
      (node (ref "C14") (pin "2") (pinfunction "2_2") (pintype "passive"))
      (node (ref "C15") (pin "-") (pinfunction "-_-") (pintype "passive"))
      (node (ref "C16") (pin "2") (pinfunction "2_2") (pintype "passive"))
      (node (ref "C17") (pin "2") (pinfunction "2_2") (pintype "passive"))
      (node (ref "C18") (pin "2") (pinfunction "2_2") (pintype "passive"))
      (node (ref "C19") (pin "2") (pinfunction "2_2") (pintype "passive"))
      (node (ref "C2") (pin "2") (pinfunction "2_2") (pintype "passive"))
      (node (ref "C20") (pin "2") (pinfunction "2_2") (pintype "passive"))
      (node (ref "C21") (pin "+") (pinfunction "+_+") (pintype "passive"))
      (node (ref "C22") (pin "2") (pinfunction "2_2") (pintype "passive"))
      (node (ref "C24") (pin "2") (pinfunction "2_2") (pintype "passive"))
      (node (ref "C25") (pin "2") (pinfunction "2_2") (pintype "passive"))
      (node (ref "C26") (pin "2") (pinfunction "2_2") (pintype "passive"))
      (node (ref "C27") (pin "2") (pinfunction "2_2") (pintype "passive"))
      (node (ref "C28") (pin "1") (pinfunction "1_1") (pintype "passive"))
      (node (ref "C29") (pin "2") (pinfunction "2_2") (pintype "passive"))
      (node (ref "C3") (pin "2") (pinfunction "2_2") (pintype "passive"))
      (node (ref "C30") (pin "2") (pinfunction "2_2") (pintype "passive"))
      (node (ref "C34") (pin "2") (pinfunction "2_2") (pintype "passive"))
      (node (ref "C35") (pin "2") (pinfunction "2_2") (pintype "passive"))
      (node (ref "C36") (pin "1") (pinfunction "1_1") (pintype "passive"))
      (node (ref "C37") (pin "1") (pinfunction "1_1") (pintype "passive"))
      (node (ref "C4") (pin "-") (pinfunction "-_-") (pintype "passive"))
      (node (ref "C41") (pin "1") (pinfunction "1_1") (pintype "passive"))
      (node (ref "C42") (pin "2") (pinfunction "2_2") (pintype "passive"))
      (node (ref "C43") (pin "2") (pinfunction "2_2") (pintype "passive"))
      (node (ref "C45") (pin "1") (pinfunction "1_1") (pintype "passive"))
      (node (ref "C47") (pin "1") (pinfunction "1_1") (pintype "passive"))
      (node (ref "C48") (pin "1") (pinfunction "1_1") (pintype "passive"))
      (node (ref "C5") (pin "-") (pinfunction "-_-") (pintype "passive"))
      (node (ref "C6") (pin "2") (pinfunction "2_2") (pintype "passive"))
      (node (ref "C7") (pin "2") (pinfunction "2_2") (pintype "passive"))
      (node (ref "C8") (pin "2") (pinfunction "2_2") (pintype "passive"))
      (node (ref "D1") (pin "A") (pinfunction "A_A") (pintype "passive"))
      (node (ref "D2") (pin "C") (pinfunction "C_C") (pintype "passive"))
      (node (ref "D3") (pin "1") (pinfunction "A_1") (pintype "passive"))
      (node (ref "IC1") (pin "1") (pinfunction "GND_1") (pintype "power_in"))
      (node (ref "IC10") (pin "8") (pinfunction "GND_8") (pintype "power_in"))
      (node (ref "IC11") (pin "3") (pinfunction "+IN_3") (pintype "input"))
      (node (ref "IC11") (pin "5") (pinfunction "+IN_5") (pintype "input"))
      (node (ref "IC12") (pin "3") (pinfunction "+IN_3") (pintype "input"))
      (node (ref "IC12") (pin "5") (pinfunction "+IN_5") (pintype "input"))
      (node (ref "IC13") (pin "3") (pinfunction "+IN_3") (pintype "input"))
      (node (ref "IC13") (pin "5") (pinfunction "+IN_5") (pintype "input"))
      (node (ref "IC2") (pin "2") (pinfunction "A_2") (pintype "passive"))
      (node (ref "IC3") (pin "6") (pinfunction "GND_6") (pintype "power_in"))
      (node (ref "IC4") (pin "1") (pinfunction "GND_1") (pintype "power_in"))
      (node (ref "IC5") (pin "2") (pinfunction "A_2") (pintype "passive"))
      (node (ref "IC7") (pin "3") (pinfunction "+IN_3") (pintype "input"))
      (node (ref "IC7") (pin "5") (pinfunction "+IN_5") (pintype "input"))
      (node (ref "IC8") (pin "3") (pinfunction "+IN_3") (pintype "input"))
      (node (ref "IC8") (pin "5") (pinfunction "+IN_5") (pintype "input"))
      (node (ref "IC9") (pin "3") (pinfunction "+IN_3") (pintype "input"))
      (node (ref "IC9") (pin "5") (pinfunction "+IN_5") (pintype "input"))
      (node (ref "J1") (pin "GND") (pinfunction "GND_GND") (pintype "passive"))
      (node (ref "J10") (pin "GND") (pinfunction "GND_GND") (pintype "passive"))
      (node (ref "J11") (pin "GND") (pinfunction "GND_GND") (pintype "passive"))
      (node (ref "J12") (pin "GND") (pinfunction "GND_GND") (pintype "passive"))
      (node (ref "J2") (pin "GND") (pinfunction "GND_GND") (pintype "passive"))
      (node (ref "J3") (pin "GND") (pinfunction "GND_GND") (pintype "passive"))
      (node (ref "J4") (pin "GND") (pinfunction "GND_GND") (pintype "passive"))
      (node (ref "J5") (pin "GND") (pinfunction "GND_GND") (pintype "passive"))
      (node (ref "J6") (pin "GND") (pinfunction "GND_GND") (pintype "passive"))
      (node (ref "J7") (pin "GND") (pinfunction "GND_GND") (pintype "passive"))
      (node (ref "J8") (pin "GND") (pinfunction "GND_GND") (pintype "passive"))
      (node (ref "J9") (pin "GND") (pinfunction "GND_GND") (pintype "passive"))
      (node (ref "JP2") (pin "3") (pinfunction "3_3") (pintype "passive"))
      (node (ref "JP2") (pin "4") (pinfunction "4_4") (pintype "passive"))
      (node (ref "JP2") (pin "5") (pinfunction "5_5") (pintype "passive"))
      (node (ref "JP2") (pin "6") (pinfunction "6_6") (pintype "passive"))
      (node (ref "JP2") (pin "7") (pinfunction "7_7") (pintype "passive"))
      (node (ref "JP2") (pin "8") (pinfunction "8_8") (pintype "passive"))
      (node (ref "JP4") (pin "3") (pinfunction "3_3") (pintype "passive"))
      (node (ref "JP4") (pin "5") (pinfunction "5_5") (pintype "passive"))
      (node (ref "JP4") (pin "9") (pinfunction "9_9") (pintype "passive"))
      (node (ref "LED5") (pin "GND") (pinfunction "C_GND") (pintype "bidirectional"))
      (node (ref "LED6") (pin "K") (pinfunction "C_K") (pintype "passive"))
      (node (ref "Q1") (pin "GND") (pinfunction "GND_GND") (pintype "bidirectional"))
      (node (ref "Q2") (pin "E") (pinfunction "E_E") (pintype "passive"))
      (node (ref "R10") (pin "1") (pinfunction "1_1") (pintype "passive"))
      (node (ref "R14") (pin "P$3") (pinfunction "A_P$3") (pintype "passive"))
      (node (ref "R2") (pin "2") (pinfunction "1_2") (pintype "bidirectional"))
      (node (ref "R2") (pin "4") (pinfunction "E_4") (pintype "bidirectional"))
      (node (ref "R24") (pin "1") (pinfunction "1_1") (pintype "passive"))
      (node (ref "R3") (pin "2") (pinfunction "1_2") (pintype "bidirectional"))
      (node (ref "R3") (pin "4") (pinfunction "E_4") (pintype "bidirectional"))
      (node (ref "R4") (pin "2") (pinfunction "1_2") (pintype "bidirectional"))
      (node (ref "R4") (pin "4") (pinfunction "E_4") (pintype "bidirectional"))
      (node (ref "R5") (pin "2") (pinfunction "1_2") (pintype "bidirectional"))
      (node (ref "R5") (pin "4") (pinfunction "E_4") (pintype "bidirectional"))
      (node (ref "R65") (pin "1") (pinfunction "1_1") (pintype "passive"))
      (node (ref "S1") (pin "1") (pinfunction "O_1") (pintype "passive"))
      (node (ref "SW3") (pin "1") (pinfunction "1_1") (pintype "passive"))
      (node (ref "SW3") (pin "2") (pinfunction "2_2") (pintype "passive"))
      (node (ref "SW4") (pin "1") (pinfunction "1_1") (pintype "passive"))
      (node (ref "SW4") (pin "2") (pinfunction "2_2") (pintype "passive"))
      (node (ref "U$1") (pin "C") (pinfunction "K_C") (pintype "bidirectional"))
      (node (ref "UC1") (pin "20") (pinfunction "PB2/BOOT1_20") (pintype "bidirectional"))
      (node (ref "UC1") (pin "23") (pinfunction "VSS_1_23") (pintype "power_in"))
      (node (ref "UC1") (pin "35") (pinfunction "VSS_2_35") (pintype "power_in"))
      (node (ref "UC1") (pin "47") (pinfunction "VSS_3_47") (pintype "power_in"))
      (node (ref "UC1") (pin "8") (pinfunction "VSS_A_8") (pintype "power_in"))
    )
    (net (code "18") (name "IN_1") (class "Default")
      (node (ref "J2") (pin "TIP") (pinfunction "TIP_TIP") (pintype "passive"))
      (node (ref "R54") (pin "1") (pinfunction "1_1") (pintype "passive"))
    )
    (net (code "19") (name "IN_2") (class "Default")
      (node (ref "J3") (pin "TIP") (pinfunction "TIP_TIP") (pintype "passive"))
      (node (ref "R33") (pin "1") (pinfunction "1_1") (pintype "passive"))
    )
    (net (code "20") (name "IN_3") (class "Default")
      (node (ref "J4") (pin "TIP") (pinfunction "TIP_TIP") (pintype "passive"))
      (node (ref "R36") (pin "1") (pinfunction "1_1") (pintype "passive"))
    )
    (net (code "21") (name "IN_4") (class "Default")
      (node (ref "J5") (pin "TIP") (pinfunction "TIP_TIP") (pintype "passive"))
      (node (ref "R57") (pin "1") (pinfunction "1_1") (pintype "passive"))
    )
    (net (code "22") (name "JTCK") (class "Default")
      (node (ref "JP4") (pin "4") (pinfunction "4_4") (pintype "passive"))
      (node (ref "UC1") (pin "37") (pinfunction "PA14/JTCK/SWCLK_37") (pintype "bidirectional"))
    )
    (net (code "23") (name "JTDI") (class "Default")
      (node (ref "JP4") (pin "8") (pinfunction "8_8") (pintype "passive"))
      (node (ref "UC1") (pin "38") (pinfunction "PA15/JTDI_38") (pintype "bidirectional"))
    )
    (net (code "24") (name "JTDO") (class "Default")
      (node (ref "JP4") (pin "6") (pinfunction "6_6") (pintype "passive"))
      (node (ref "UC1") (pin "39") (pinfunction "PB3/JTDO_39") (pintype "bidirectional"))
    )
    (net (code "25") (name "JTMS") (class "Default")
      (node (ref "JP4") (pin "2") (pinfunction "2_2") (pintype "passive"))
      (node (ref "UC1") (pin "34") (pinfunction "PA13/JTMS/SWDIO_34") (pintype "bidirectional"))
    )
    (net (code "26") (name "LED_B") (class "Default")
      (node (ref "R12") (pin "1") (pinfunction "1_1") (pintype "passive"))
      (node (ref "UC1") (pin "18") (pinfunction "PB0/ADC12_IN8/TIM3_CH3_18") (pintype "bidirectional"))
    )
    (net (code "27") (name "LED_CH1") (class "Default")
      (node (ref "R6") (pin "2") (pinfunction "2_2") (pintype "passive"))
      (node (ref "UC1") (pin "46") (pinfunction "PB9/TIM4_CH4_46") (pintype "input"))
    )
    (net (code "28") (name "LED_CH2") (class "Default")
      (node (ref "R7") (pin "2") (pinfunction "2_2") (pintype "passive"))
      (node (ref "UC1") (pin "45") (pinfunction "PB8/TIM4_CH3_45") (pintype "bidirectional"))
    )
    (net (code "29") (name "LED_CH3") (class "Default")
      (node (ref "R8") (pin "2") (pinfunction "2_2") (pintype "passive"))
      (node (ref "UC1") (pin "43") (pinfunction "PB7/I2C1_SDA/TIM4_CH2_43") (pintype "bidirectional"))
    )
    (net (code "30") (name "LED_CH4") (class "Default")
      (node (ref "R9") (pin "2") (pinfunction "2_2") (pintype "passive"))
      (node (ref "UC1") (pin "42") (pinfunction "PB6/I2C1_SCL/TIM4_CH1_42") (pintype "input"))
    )
    (net (code "31") (name "LED_FRAME") (class "Default")
      (node (ref "R16") (pin "1") (pinfunction "1_1") (pintype "passive"))
      (node (ref "UC1") (pin "41") (pinfunction "PB5/I2C1_SMBA_41") (pintype "input"))
    )
    (net (code "32") (name "LED_G") (class "Default")
      (node (ref "R11") (pin "1") (pinfunction "1_1") (pintype "passive"))
      (node (ref "UC1") (pin "17") (pinfunction "PA7/SPI1_MOSI/ADC12_IN7/TIM3_CH2_17") (pintype "bidirectional"))
    )
    (net (code "33") (name "LED_R") (class "Default")
      (node (ref "R13") (pin "1") (pinfunction "1_1") (pintype "passive"))
      (node (ref "UC1") (pin "19") (pinfunction "PB1/ADC12_IN9/TIM3_CH4_19") (pintype "bidirectional"))
    )
    (net (code "34") (name "MODULATION") (class "Default")
      (node (ref "D3") (pin "3") (pinfunction "AC_3") (pintype "passive"))
      (node (ref "R39") (pin "2") (pinfunction "2_2") (pintype "passive"))
      (node (ref "UC1") (pin "14") (pinfunction "PA4/SPI1_NSS/USART2_CK/ADC12_IN4_14") (pintype "bidirectional"))
    )
    (net (code "35") (name "Net-(C22-Pad1)") (class "Default")
      (node (ref "C22") (pin "1") (pinfunction "1_1") (pintype "passive"))
      (node (ref "R34") (pin "1") (pinfunction "1_1") (pintype "passive"))
    )
    (net (code "36") (name "Net-(C27-Pad1)") (class "Default")
      (node (ref "C27") (pin "1") (pinfunction "1_1") (pintype "passive"))
      (node (ref "R35") (pin "1") (pinfunction "1_1") (pintype "passive"))
    )
    (net (code "37") (name "Net-(C42-Pad1)") (class "Default")
      (node (ref "C42") (pin "1") (pinfunction "1_1") (pintype "passive"))
      (node (ref "R55") (pin "1") (pinfunction "1_1") (pintype "passive"))
    )
    (net (code "38") (name "Net-(C43-Pad1)") (class "Default")
      (node (ref "C43") (pin "1") (pinfunction "1_1") (pintype "passive"))
      (node (ref "R56") (pin "1") (pinfunction "1_1") (pintype "passive"))
    )
    (net (code "39") (name "Net-(IC3-OUTA)") (class "Default")
      (node (ref "IC3") (pin "2") (pinfunction "OUTA_2") (pintype "output"))
      (node (ref "R19") (pin "1") (pinfunction "1_1") (pintype "passive"))
    )
    (net (code "40") (name "Net-(IC3-OUTB)") (class "Default")
      (node (ref "IC3") (pin "3") (pinfunction "OUTB_3") (pintype "output"))
      (node (ref "R20") (pin "1") (pinfunction "1_1") (pintype "passive"))
    )
    (net (code "41") (name "Net-(IC3-OUTC)") (class "Default")
      (node (ref "IC3") (pin "4") (pinfunction "OUTC_4") (pintype "output"))
      (node (ref "R21") (pin "1") (pinfunction "1_1") (pintype "passive"))
    )
    (net (code "42") (name "Net-(IC3-OUTD)") (class "Default")
      (node (ref "IC3") (pin "5") (pinfunction "OUTD_5") (pintype "output"))
      (node (ref "R22") (pin "1") (pinfunction "1_1") (pintype "passive"))
    )
    (net (code "43") (name "Net-(IC5-C)") (class "Default")
      (node (ref "IC5") (pin "1") (pinfunction "C_1") (pintype "passive"))
      (node (ref "IC6") (pin "5") (pinfunction "+IN_5") (pintype "input"))
      (node (ref "R26") (pin "2") (pinfunction "2_2") (pintype "passive"))
      (node (ref "R27") (pin "2") (pinfunction "2_2") (pintype "passive"))
    )
    (net (code "44") (name "Net-(IC6A-+IN)") (class "Default")
      (node (ref "IC6") (pin "3") (pinfunction "+IN_3") (pintype "input"))
      (node (ref "R27") (pin "1") (pinfunction "1_1") (pintype "passive"))
      (node (ref "R65") (pin "2") (pinfunction "2_2") (pintype "passive"))
    )
    (net (code "45") (name "Net-(IC7A--IN)") (class "Default")
      (node (ref "C38") (pin "1") (pinfunction "1_1") (pintype "passive"))
      (node (ref "IC7") (pin "2") (pinfunction "-IN_2") (pintype "input"))
      (node (ref "R43") (pin "1") (pinfunction "1_1") (pintype "passive"))
      (node (ref "R44") (pin "2") (pinfunction "2_2") (pintype "passive"))
      (node (ref "R45") (pin "2") (pinfunction "2_2") (pintype "passive"))
      (node (ref "R46") (pin "2") (pinfunction "2_2") (pintype "passive"))
      (node (ref "R47") (pin "2") (pinfunction "2_2") (pintype "passive"))
    )
    (net (code "46") (name "Net-(IC7A-OUT)") (class "Default")
      (node (ref "C38") (pin "2") (pinfunction "2_2") (pintype "passive"))
      (node (ref "IC7") (pin "1") (pinfunction "OUT_1") (pintype "output"))
      (node (ref "R30") (pin "1") (pinfunction "1_1") (pintype "passive"))
      (node (ref "R43") (pin "2") (pinfunction "2_2") (pintype "passive"))
    )
    (net (code "47") (name "Net-(IC7B--IN)") (class "Default")
      (node (ref "C23") (pin "1") (pinfunction "1_1") (pintype "passive"))
      (node (ref "IC7") (pin "6") (pinfunction "-IN_6") (pintype "input"))
      (node (ref "R29") (pin "1") (pinfunction "1_1") (pintype "passive"))
      (node (ref "R30") (pin "2") (pinfunction "2_2") (pintype "passive"))
    )
    (net (code "48") (name "Net-(IC7B-OUT)") (class "Default")
      (node (ref "C23") (pin "2") (pinfunction "2_2") (pintype "passive"))
      (node (ref "IC7") (pin "7") (pinfunction "OUT_7") (pintype "output"))
      (node (ref "R28") (pin "1") (pinfunction "1_1") (pintype "passive"))
      (node (ref "R29") (pin "2") (pinfunction "2_2") (pintype "passive"))
    )
    (net (code "49") (name "Net-(IC8A--IN)") (class "Default")
      (node (ref "C39") (pin "1") (pinfunction "1_1") (pintype "passive"))
      (node (ref "IC8") (pin "2") (pinfunction "-IN_2") (pintype "input"))
      (node (ref "R49") (pin "1") (pinfunction "1_1") (pintype "passive"))
      (node (ref "R50") (pin "2") (pinfunction "2_2") (pintype "passive"))
    )
    (net (code "50") (name "Net-(IC8A-OUT)") (class "Default")
      (node (ref "C39") (pin "2") (pinfunction "2_2") (pintype "passive"))
      (node (ref "IC8") (pin "1") (pinfunction "OUT_1") (pintype "output"))
      (node (ref "R48") (pin "1") (pinfunction "1_1") (pintype "passive"))
      (node (ref "R49") (pin "2") (pinfunction "2_2") (pintype "passive"))
    )
    (net (code "51") (name "Net-(IC8B-OUT)") (class "Default")
      (node (ref "IC8") (pin "7") (pinfunction "OUT_7") (pintype "output"))
      (node (ref "R31") (pin "2") (pinfunction "2_2") (pintype "passive"))
      (node (ref "R50") (pin "1") (pinfunction "1_1") (pintype "passive"))
    )
    (net (code "52") (name "Net-(IC9A--IN)") (class "Default")
      (node (ref "C40") (pin "1") (pinfunction "1_1") (pintype "passive"))
      (node (ref "IC9") (pin "2") (pinfunction "-IN_2") (pintype "input"))
      (node (ref "R52") (pin "1") (pinfunction "1_1") (pintype "passive"))
      (node (ref "R53") (pin "2") (pinfunction "2_2") (pintype "passive"))
    )
    (net (code "53") (name "Net-(IC9A-OUT)") (class "Default")
      (node (ref "C40") (pin "2") (pinfunction "2_2") (pintype "passive"))
      (node (ref "IC9") (pin "1") (pinfunction "OUT_1") (pintype "output"))
      (node (ref "R51") (pin "1") (pinfunction "1_1") (pintype "passive"))
      (node (ref "R52") (pin "2") (pinfunction "2_2") (pintype "passive"))
    )
    (net (code "54") (name "Net-(IC9B-OUT)") (class "Default")
      (node (ref "IC9") (pin "7") (pinfunction "OUT_7") (pintype "output"))
      (node (ref "R32") (pin "2") (pinfunction "2_2") (pintype "passive"))
      (node (ref "R53") (pin "1") (pinfunction "1_1") (pintype "passive"))
    )
    (net (code "55") (name "Net-(IC10A-IN)") (class "Default")
      (node (ref "IC10") (pin "2") (pinfunction "IN_2") (pintype "input"))
      (node (ref "R54") (pin "2") (pinfunction "2_2") (pintype "passive"))
      (node (ref "R55") (pin "2") (pinfunction "2_2") (pintype "passive"))
    )
    (net (code "56") (name "Net-(IC10A-OUT)") (class "Default")
      (node (ref "IC10") (pin "4") (pinfunction "OUT_4") (pintype "output"))
      (node (ref "IC8") (pin "6") (pinfunction "-IN_6") (pintype "input"))
      (node (ref "R31") (pin "1") (pinfunction "1_1") (pintype "passive"))
    )
    (net (code "57") (name "Net-(IC10B-IN)") (class "Default")
      (node (ref "IC10") (pin "7") (pinfunction "IN_7") (pintype "input"))
      (node (ref "R56") (pin "2") (pinfunction "2_2") (pintype "passive"))
      (node (ref "R57") (pin "2") (pinfunction "2_2") (pintype "passive"))
    )
    (net (code "58") (name "Net-(IC10B-OUT)") (class "Default")
      (node (ref "IC10") (pin "5") (pinfunction "OUT_5") (pintype "output"))
      (node (ref "IC12") (pin "6") (pinfunction "-IN_6") (pintype "input"))
      (node (ref "R38") (pin "1") (pinfunction "1_1") (pintype "passive"))
    )
    (net (code "59") (name "Net-(IC10C-IN)") (class "Default")
      (node (ref "IC10") (pin "10") (pinfunction "IN_10") (pintype "input"))
      (node (ref "R35") (pin "2") (pinfunction "2_2") (pintype "passive"))
      (node (ref "R36") (pin "2") (pinfunction "2_2") (pintype "passive"))
    )
    (net (code "60") (name "Net-(IC10C-OUT)") (class "Default")
      (node (ref "IC10") (pin "12") (pinfunction "OUT_12") (pintype "output"))
      (node (ref "IC11") (pin "6") (pinfunction "-IN_6") (pintype "input"))
      (node (ref "R37") (pin "1") (pinfunction "1_1") (pintype "passive"))
    )
    (net (code "61") (name "Net-(IC10D-IN)") (class "Default")
      (node (ref "IC10") (pin "15") (pinfunction "IN_15") (pintype "input"))
      (node (ref "R33") (pin "2") (pinfunction "2_2") (pintype "passive"))
      (node (ref "R34") (pin "2") (pinfunction "2_2") (pintype "passive"))
    )
    (net (code "62") (name "Net-(IC10D-OUT)") (class "Default")
      (node (ref "IC10") (pin "13") (pinfunction "OUT_13") (pintype "output"))
      (node (ref "IC9") (pin "6") (pinfunction "-IN_6") (pintype "input"))
      (node (ref "R32") (pin "1") (pinfunction "1_1") (pintype "passive"))
    )
    (net (code "63") (name "Net-(IC11A--IN)") (class "Default")
      (node (ref "C44") (pin "1") (pinfunction "1_1") (pintype "passive"))
      (node (ref "IC11") (pin "2") (pinfunction "-IN_2") (pintype "input"))
      (node (ref "R59") (pin "1") (pinfunction "1_1") (pintype "passive"))
      (node (ref "R60") (pin "2") (pinfunction "2_2") (pintype "passive"))
    )
    (net (code "64") (name "Net-(IC11A-OUT)") (class "Default")
      (node (ref "C44") (pin "2") (pinfunction "2_2") (pintype "passive"))
      (node (ref "IC11") (pin "1") (pinfunction "OUT_1") (pintype "output"))
      (node (ref "R58") (pin "1") (pinfunction "1_1") (pintype "passive"))
      (node (ref "R59") (pin "2") (pinfunction "2_2") (pintype "passive"))
    )
    (net (code "65") (name "Net-(IC11B-OUT)") (class "Default")
      (node (ref "IC11") (pin "7") (pinfunction "OUT_7") (pintype "output"))
      (node (ref "R37") (pin "2") (pinfunction "2_2") (pintype "passive"))
      (node (ref "R60") (pin "1") (pinfunction "1_1") (pintype "passive"))
    )
    (net (code "66") (name "Net-(IC12A--IN)") (class "Default")
      (node (ref "C46") (pin "1") (pinfunction "1_1") (pintype "passive"))
      (node (ref "IC12") (pin "2") (pinfunction "-IN_2") (pintype "input"))
      (node (ref "R62") (pin "1") (pinfunction "1_1") (pintype "passive"))
      (node (ref "R63") (pin "2") (pinfunction "2_2") (pintype "passive"))
    )
    (net (code "67") (name "Net-(IC12A-OUT)") (class "Default")
      (node (ref "C46") (pin "2") (pinfunction "2_2") (pintype "passive"))
      (node (ref "IC12") (pin "1") (pinfunction "OUT_1") (pintype "output"))
      (node (ref "R61") (pin "1") (pinfunction "1_1") (pintype "passive"))
      (node (ref "R62") (pin "2") (pinfunction "2_2") (pintype "passive"))
    )
    (net (code "68") (name "Net-(IC12B-OUT)") (class "Default")
      (node (ref "IC12") (pin "7") (pinfunction "OUT_7") (pintype "output"))
      (node (ref "R38") (pin "2") (pinfunction "2_2") (pintype "passive"))
      (node (ref "R63") (pin "1") (pinfunction "1_1") (pintype "passive"))
    )
    (net (code "69") (name "Net-(IC13A--IN)") (class "Default")
      (node (ref "IC13") (pin "2") (pinfunction "-IN_2") (pintype "input"))
      (node (ref "R15") (pin "P$3") (pinfunction "3_P$3") (pintype "passive"))
      (node (ref "R64") (pin "1") (pinfunction "1_1") (pintype "passive"))
    )
    (net (code "70") (name "Net-(IC13A-OUT)") (class "Default")
      (node (ref "IC13") (pin "1") (pinfunction "OUT_1") (pintype "output"))
      (node (ref "R41") (pin "1") (pinfunction "1_1") (pintype "passive"))
      (node (ref "R64") (pin "2") (pinfunction "2_2") (pintype "passive"))
    )
    (net (code "71") (name "Net-(IC13B--IN)") (class "Default")
      (node (ref "C31") (pin "1") (pinfunction "1_1") (pintype "passive"))
      (node (ref "IC13") (pin "6") (pinfunction "-IN_6") (pintype "input"))
      (node (ref "R15") (pin "P$1") (pinfunction "1_P$1") (pintype "passive"))
      (node (ref "R40") (pin "1") (pinfunction "1_1") (pintype "passive"))
      (node (ref "R41") (pin "2") (pinfunction "2_2") (pintype "passive"))
      (node (ref "R42") (pin "2") (pinfunction "2_2") (pintype "passive"))
    )
    (net (code "72") (name "Net-(IC13B-OUT)") (class "Default")
      (node (ref "C31") (pin "2") (pinfunction "2_2") (pintype "passive"))
      (node (ref "IC13") (pin "7") (pinfunction "OUT_7") (pintype "output"))
      (node (ref "R39") (pin "1") (pinfunction "1_1") (pintype "passive"))
      (node (ref "R40") (pin "2") (pinfunction "2_2") (pintype "passive"))
    )
    (net (code "73") (name "Net-(J6-PadTIP)") (class "Default")
      (node (ref "J6") (pin "TIP") (pinfunction "TIP_TIP") (pintype "passive"))
      (node (ref "R18") (pin "1") (pinfunction "1_1") (pintype "passive"))
    )
    (net (code "74") (name "Net-(J7-PadTIP)") (class "Default")
      (node (ref "J7") (pin "TIP") (pinfunction "TIP_TIP") (pintype "passive"))
      (node (ref "R28") (pin "2") (pinfunction "2_2") (pintype "passive"))
    )
    (net (code "75") (name "Net-(J8-PadTIP)") (class "Default")
      (node (ref "J8") (pin "TIP") (pinfunction "TIP_TIP") (pintype "passive"))
      (node (ref "R48") (pin "2") (pinfunction "2_2") (pintype "passive"))
    )
    (net (code "76") (name "Net-(J9-PadTIP)") (class "Default")
      (node (ref "J9") (pin "TIP") (pinfunction "TIP_TIP") (pintype "passive"))
      (node (ref "R51") (pin "2") (pinfunction "2_2") (pintype "passive"))
    )
    (net (code "77") (name "Net-(J10-PadTIP)") (class "Default")
      (node (ref "J10") (pin "TIP") (pinfunction "TIP_TIP") (pintype "passive"))
      (node (ref "R58") (pin "2") (pinfunction "2_2") (pintype "passive"))
    )
    (net (code "78") (name "Net-(J11-PadTIP)") (class "Default")
      (node (ref "J11") (pin "TIP") (pinfunction "TIP_TIP") (pintype "passive"))
      (node (ref "R61") (pin "2") (pinfunction "2_2") (pintype "passive"))
    )
    (net (code "79") (name "Net-(J12-PadTIP)") (class "Default")
      (node (ref "J12") (pin "TIP") (pinfunction "TIP_TIP") (pintype "passive"))
      (node (ref "Q2") (pin "C") (pinfunction "C_C") (pintype "passive"))
      (node (ref "R24") (pin "2") (pinfunction "2_2") (pintype "passive"))
      (node (ref "R25") (pin "1") (pinfunction "1_1") (pintype "passive"))
    )
    (net (code "80") (name "Net-(JP2-Pad1)") (class "Default")
      (node (ref "JP2") (pin "1") (pinfunction "1_1") (pintype "passive"))
      (node (ref "JP2") (pin "2") (pinfunction "2_2") (pintype "passive"))
      (node (ref "P1") (pin "2") (pinfunction "2_2") (pintype "bidirectional"))
    )
    (net (code "81") (name "Net-(JP2-Pad10)") (class "Default")
      (node (ref "JP2") (pin "10") (pinfunction "10_10") (pintype "passive"))
      (node (ref "JP2") (pin "9") (pinfunction "9_9") (pintype "passive"))
      (node (ref "P2") (pin "2") (pinfunction "2_2") (pintype "bidirectional"))
    )
    (net (code "82") (name "Net-(LED5-PadBLU)") (class "Default")
      (node (ref "LED5") (pin "BLU") (pinfunction "BLU_BLU") (pintype "bidirectional"))
      (node (ref "R12") (pin "2") (pinfunction "2_2") (pintype "passive"))
    )
    (net (code "83") (name "Net-(LED5-PadGRN)") (class "Default")
      (node (ref "LED5") (pin "GRN") (pinfunction "GRN_GRN") (pintype "bidirectional"))
      (node (ref "R11") (pin "2") (pinfunction "2_2") (pintype "passive"))
    )
    (net (code "84") (name "Net-(LED5-PadRED)") (class "Default")
      (node (ref "LED5") (pin "RED") (pinfunction "RED_RED") (pintype "bidirectional"))
      (node (ref "R13") (pin "2") (pinfunction "2_2") (pintype "passive"))
    )
    (net (code "85") (name "Net-(LED6-PadA)") (class "Default")
      (node (ref "LED6") (pin "A") (pinfunction "A_A") (pintype "passive"))
      (node (ref "R16") (pin "2") (pinfunction "2_2") (pintype "passive"))
    )
    (net (code "86") (name "Net-(Q2-PadB)") (class "Default")
      (node (ref "Q2") (pin "B") (pinfunction "B_B") (pintype "passive"))
      (node (ref "R23") (pin "2") (pinfunction "2_2") (pintype "passive"))
    )
    (net (code "87") (name "Net-(R2-B)") (class "Default")
      (node (ref "R2") (pin "5") (pinfunction "B_5") (pintype "bidirectional"))
      (node (ref "R6") (pin "1") (pinfunction "1_1") (pintype "passive"))
    )
    (net (code "88") (name "Net-(R3-B)") (class "Default")
      (node (ref "R3") (pin "5") (pinfunction "B_5") (pintype "bidirectional"))
      (node (ref "R7") (pin "1") (pinfunction "1_1") (pintype "passive"))
    )
    (net (code "89") (name "Net-(R4-B)") (class "Default")
      (node (ref "R4") (pin "5") (pinfunction "B_5") (pintype "bidirectional"))
      (node (ref "R8") (pin "1") (pinfunction "1_1") (pintype "passive"))
    )
    (net (code "90") (name "Net-(R5-B)") (class "Default")
      (node (ref "R5") (pin "5") (pinfunction "B_5") (pintype "bidirectional"))
      (node (ref "R9") (pin "1") (pinfunction "1_1") (pintype "passive"))
    )
    (net (code "91") (name "Net-(R15-2)") (class "Default")
      (node (ref "R15") (pin "P$2") (pinfunction "2_P$2") (pintype "passive"))
      (node (ref "R18") (pin "2") (pinfunction "2_2") (pintype "passive"))
    )
    (net (code "92") (name "Net-(S1-P)") (class "Default")
      (node (ref "J1") (pin "NORM") (pinfunction "NORM_NORM") (pintype "passive"))
      (node (ref "S1") (pin "2") (pinfunction "P_2") (pintype "passive"))
    )
    (net (code "93") (name "Net-(S1-S)") (class "Default")
      (node (ref "JP1") (pin "2") (pinfunction "2_2") (pintype "passive"))
      (node (ref "S1") (pin "3") (pinfunction "S_3") (pintype "passive"))
    )
    (net (code "94") (name "Net-(UC1-PD0-OSC_IN)") (class "Default")
      (node (ref "Q1") (pin "X1") (pinfunction "X1_X1") (pintype "bidirectional"))
      (node (ref "UC1") (pin "5") (pinfunction "PD0-OSC_IN_5") (pintype "input"))
    )
    (net (code "95") (name "Net-(UC1-PD1-OSC_OUT)") (class "Default")
      (node (ref "Q1") (pin "X2") (pinfunction "X2_X2") (pintype "bidirectional"))
      (node (ref "UC1") (pin "6") (pinfunction "PD1-OSC_OUT_6") (pintype "input"))
    )
    (net (code "96") (name "PAN") (class "Default")
      (node (ref "J1") (pin "TIP") (pinfunction "TIP_TIP") (pintype "passive"))
      (node (ref "J2") (pin "NORM") (pinfunction "NORM_NORM") (pintype "passive"))
      (node (ref "J3") (pin "NORM") (pinfunction "NORM_NORM") (pintype "passive"))
      (node (ref "J4") (pin "NORM") (pinfunction "NORM_NORM") (pintype "passive"))
      (node (ref "J5") (pin "NORM") (pinfunction "NORM_NORM") (pintype "passive"))
    )
    (net (code "97") (name "POT_CH1") (class "Default")
      (node (ref "R2") (pin "1") (pinfunction "2_1") (pintype "bidirectional"))
      (node (ref "UC1") (pin "10") (pinfunction "PA0_WKUP/USART2_CTS/ADC12_IN0/TIM2_CH1_ETR_10") (pintype "bidirectional"))
    )
    (net (code "98") (name "POT_CH2") (class "Default")
      (node (ref "R3") (pin "1") (pinfunction "2_1") (pintype "bidirectional"))
      (node (ref "UC1") (pin "11") (pinfunction "PA1/USART2_RTS/ADC12_IN1/TIM2_CH2_11") (pintype "bidirectional"))
    )
    (net (code "99") (name "POT_CH3") (class "Default")
      (node (ref "R4") (pin "1") (pinfunction "2_1") (pintype "bidirectional"))
      (node (ref "UC1") (pin "12") (pinfunction "PA2/USART2_TX/ADC12_IN2/TIM2_CH3_12") (pintype "bidirectional"))
    )
    (net (code "100") (name "POT_CH4") (class "Default")
      (node (ref "R5") (pin "1") (pinfunction "2_1") (pintype "bidirectional"))
      (node (ref "UC1") (pin "13") (pinfunction "PA3/USART2_RX/ADC12_IN3/TIM2_CH4_13") (pintype "bidirectional"))
    )
    (net (code "101") (name "POT_FRAME") (class "Default")
      (node (ref "R14") (pin "P$2") (pinfunction "S_P$2") (pintype "passive"))
      (node (ref "UC1") (pin "15") (pinfunction "PA5/SPI1_SCK/ADC12_IN5_15") (pintype "bidirectional"))
    )
    (net (code "102") (name "RESET") (class "Default")
      (node (ref "JP4") (pin "10") (pinfunction "10_10") (pintype "passive"))
      (node (ref "R1") (pin "1") (pinfunction "1_1") (pintype "passive"))
      (node (ref "UC1") (pin "7") (pinfunction "NRST_7") (pintype "input"))
    )
    (net (code "103") (name "RX") (class "Default")
      (node (ref "UC1") (pin "31") (pinfunction "PA10/USART1_RX/TIM1_CH3_31") (pintype "bidirectional"))
    )
    (net (code "104") (name "TX") (class "Default")
      (node (ref "UC1") (pin "30") (pinfunction "PA9/USART1_TX/TIM1_CH2_30") (pintype "input"))
    )
    (net (code "105") (name "VCA_1") (class "Default")
      (node (ref "J8") (pin "NORM") (pinfunction "NORM_NORM") (pintype "passive"))
      (node (ref "R44") (pin "1") (pinfunction "1_1") (pintype "passive"))
    )
    (net (code "106") (name "VCA_2") (class "Default")
      (node (ref "J9") (pin "NORM") (pinfunction "NORM_NORM") (pintype "passive"))
      (node (ref "R47") (pin "1") (pinfunction "1_1") (pintype "passive"))
    )
    (net (code "107") (name "VCA_3") (class "Default")
      (node (ref "J10") (pin "NORM") (pinfunction "NORM_NORM") (pintype "passive"))
      (node (ref "R46") (pin "1") (pinfunction "1_1") (pintype "passive"))
    )
    (net (code "108") (name "VCA_4") (class "Default")
      (node (ref "J11") (pin "NORM") (pinfunction "NORM_NORM") (pintype "passive"))
      (node (ref "R45") (pin "1") (pinfunction "1_1") (pintype "passive"))
    )
    (net (code "109") (name "VCC") (class "Default")
      (node (ref "C11") (pin "+") (pinfunction "+_+") (pintype "passive"))
      (node (ref "C24") (pin "1") (pinfunction "1_1") (pintype "passive"))
      (node (ref "C25") (pin "1") (pinfunction "1_1") (pintype "passive"))
      (node (ref "C26") (pin "1") (pinfunction "1_1") (pintype "passive"))
      (node (ref "C29") (pin "1") (pinfunction "1_1") (pintype "passive"))
      (node (ref "C30") (pin "1") (pinfunction "1_1") (pintype "passive"))
      (node (ref "C34") (pin "1") (pinfunction "1_1") (pintype "passive"))
      (node (ref "C35") (pin "1") (pinfunction "1_1") (pintype "passive"))
      (node (ref "C4") (pin "+") (pinfunction "+_+") (pintype "passive"))
      (node (ref "D1") (pin "C") (pinfunction "C_C") (pintype "passive"))
      (node (ref "IC1") (pin "3") (pinfunction "VIN_3") (pintype "input"))
      (node (ref "IC10") (pin "16") (pinfunction "V+_16") (pintype "power_in"))
      (node (ref "IC11") (pin "8") (pinfunction "V+_8") (pintype "power_in"))
      (node (ref "IC12") (pin "8") (pinfunction "V+_8") (pintype "power_in"))
      (node (ref "IC13") (pin "8") (pinfunction "V+_8") (pintype "power_in"))
      (node (ref "IC4") (pin "3") (pinfunction "VIN_3") (pintype "input"))
      (node (ref "IC6") (pin "8") (pinfunction "V+_8") (pintype "power_in"))
      (node (ref "IC7") (pin "8") (pinfunction "V+_8") (pintype "power_in"))
      (node (ref "IC8") (pin "8") (pinfunction "V+_8") (pintype "power_in"))
      (node (ref "IC9") (pin "8") (pinfunction "V+_8") (pintype "power_in"))
      (node (ref "P1") (pin "1") (pinfunction "1_1") (pintype "bidirectional"))
      (node (ref "R25") (pin "2") (pinfunction "2_2") (pintype "passive"))
      (node (ref "R26") (pin "1") (pinfunction "1_1") (pintype "passive"))
    )
    (net (code "110") (name "VEE") (class "Default")
      (node (ref "C21") (pin "-") (pinfunction "-_-") (pintype "passive"))
      (node (ref "C28") (pin "2") (pinfunction "2_2") (pintype "passive"))
      (node (ref "C36") (pin "2") (pinfunction "2_2") (pintype "passive"))
      (node (ref "C37") (pin "2") (pinfunction "2_2") (pintype "passive"))
      (node (ref "C41") (pin "2") (pinfunction "2_2") (pintype "passive"))
      (node (ref "C45") (pin "2") (pinfunction "2_2") (pintype "passive"))
      (node (ref "C47") (pin "2") (pinfunction "2_2") (pintype "passive"))
      (node (ref "C48") (pin "2") (pinfunction "2_2") (pintype "passive"))
      (node (ref "D2") (pin "A") (pinfunction "A_A") (pintype "passive"))
      (node (ref "IC10") (pin "9") (pinfunction "V-_9") (pintype "power_in"))
      (node (ref "IC11") (pin "4") (pinfunction "V-_4") (pintype "power_in"))
      (node (ref "IC12") (pin "4") (pinfunction "V-_4") (pintype "power_in"))
      (node (ref "IC13") (pin "4") (pinfunction "V-_4") (pintype "power_in"))
      (node (ref "IC6") (pin "4") (pinfunction "V-_4") (pintype "power_in"))
      (node (ref "IC7") (pin "4") (pinfunction "V-_4") (pintype "power_in"))
      (node (ref "IC8") (pin "4") (pinfunction "V-_4") (pintype "power_in"))
      (node (ref "IC9") (pin "4") (pinfunction "V-_4") (pintype "power_in"))
      (node (ref "P2") (pin "1") (pinfunction "1_1") (pintype "bidirectional"))
      (node (ref "R42") (pin "1") (pinfunction "1_1") (pintype "passive"))
      (node (ref "U$1") (pin "A") (pinfunction "A_A") (pintype "bidirectional"))
    )
    (net (code "111") (name "unconnected-(IC10E-MODE-Pad1)") (class "Default")
      (node (ref "IC10") (pin "1") (pinfunction "MODE_1") (pintype "input"))
    )
    (net (code "112") (name "unconnected-(J6-PadNORM)") (class "Default")
      (node (ref "J6") (pin "NORM") (pinfunction "NORM_NORM") (pintype "passive"))
    )
    (net (code "113") (name "unconnected-(J7-PadNORM)") (class "Default")
      (node (ref "J7") (pin "NORM") (pinfunction "NORM_NORM") (pintype "passive"))
    )
    (net (code "114") (name "unconnected-(J12-PadNORM)") (class "Default")
      (node (ref "J12") (pin "NORM") (pinfunction "NORM_NORM") (pintype "passive"))
    )
    (net (code "115") (name "unconnected-(JP4-Pad7)") (class "Default")
      (node (ref "JP4") (pin "7") (pinfunction "7_7") (pintype "passive"))
    )
    (net (code "116") (name "unconnected-(R2-L-Pad3)") (class "Default")
      (node (ref "R2") (pin "3") (pinfunction "L_3") (pintype "bidirectional"))
    )
    (net (code "117") (name "unconnected-(R3-L-Pad3)") (class "Default")
      (node (ref "R3") (pin "3") (pinfunction "L_3") (pintype "bidirectional"))
    )
    (net (code "118") (name "unconnected-(R4-L-Pad3)") (class "Default")
      (node (ref "R4") (pin "3") (pinfunction "L_3") (pintype "bidirectional"))
    )
    (net (code "119") (name "unconnected-(R5-L-Pad3)") (class "Default")
      (node (ref "R5") (pin "3") (pinfunction "L_3") (pintype "bidirectional"))
    )
    (net (code "120") (name "unconnected-(UC1-PA8{slash}USART1_CK{slash}TIM1_CH1{slash}MCO-Pad29)") (class "Default")
      (node (ref "UC1") (pin "29") (pinfunction "PA8/USART1_CK/TIM1_CH1/MCO_29") (pintype "bidirectional"))
    )
    (net (code "121") (name "unconnected-(UC1-PA11{slash}USART1_CTS{slash}CAN_RX{slash}TIM1_CH4{slash}USBDM-Pad32)") (class "Default")
      (node (ref "UC1") (pin "32") (pinfunction "PA11/USART1_CTS/CAN_RX/TIM1_CH4/USBDM_32") (pintype "bidirectional"))
    )
    (net (code "122") (name "unconnected-(UC1-PA12{slash}USART1_RTS{slash}CAN_TX{slash}TIM1_ETR{slash}USBDP-Pad33)") (class "Default")
      (node (ref "UC1") (pin "33") (pinfunction "PA12/USART1_RTS/CAN_TX/TIM1_ETR/USBDP_33") (pintype "bidirectional"))
    )
    (net (code "123") (name "unconnected-(UC1-PB4{slash}NJTRST-Pad40)") (class "Default")
      (node (ref "UC1") (pin "40") (pinfunction "PB4/NJTRST_40") (pintype "bidirectional"))
    )
    (net (code "124") (name "unconnected-(UC1-PB14{slash}SPI2_MISO{slash}USART3_RTS{slash}TIM1_CH2N-Pad27)") (class "Default")
      (node (ref "UC1") (pin "27") (pinfunction "PB14/SPI2_MISO/USART3_RTS/TIM1_CH2N_27") (pintype "input"))
    )
    (net (code "125") (name "unconnected-(UC1-PC13-TAMPER-RTC-Pad2)") (class "Default")
      (node (ref "UC1") (pin "2") (pinfunction "PC13-TAMPER-RTC_2") (pintype "input"))
    )
    (net (code "126") (name "unconnected-(UC1-PC14-OSC32_IN-Pad3)") (class "Default")
      (node (ref "UC1") (pin "3") (pinfunction "PC14-OSC32_IN_3") (pintype "input"))
    )
    (net (code "127") (name "unconnected-(UC1-PC15-OSC32_OUT-Pad4)") (class "Default")
      (node (ref "UC1") (pin "4") (pinfunction "PC15-OSC32_OUT_4") (pintype "input"))
    )
  )
)
